# SCH_PicoCounter_v2.net
KiCad netlist of a schematic drawn in EasyEDA
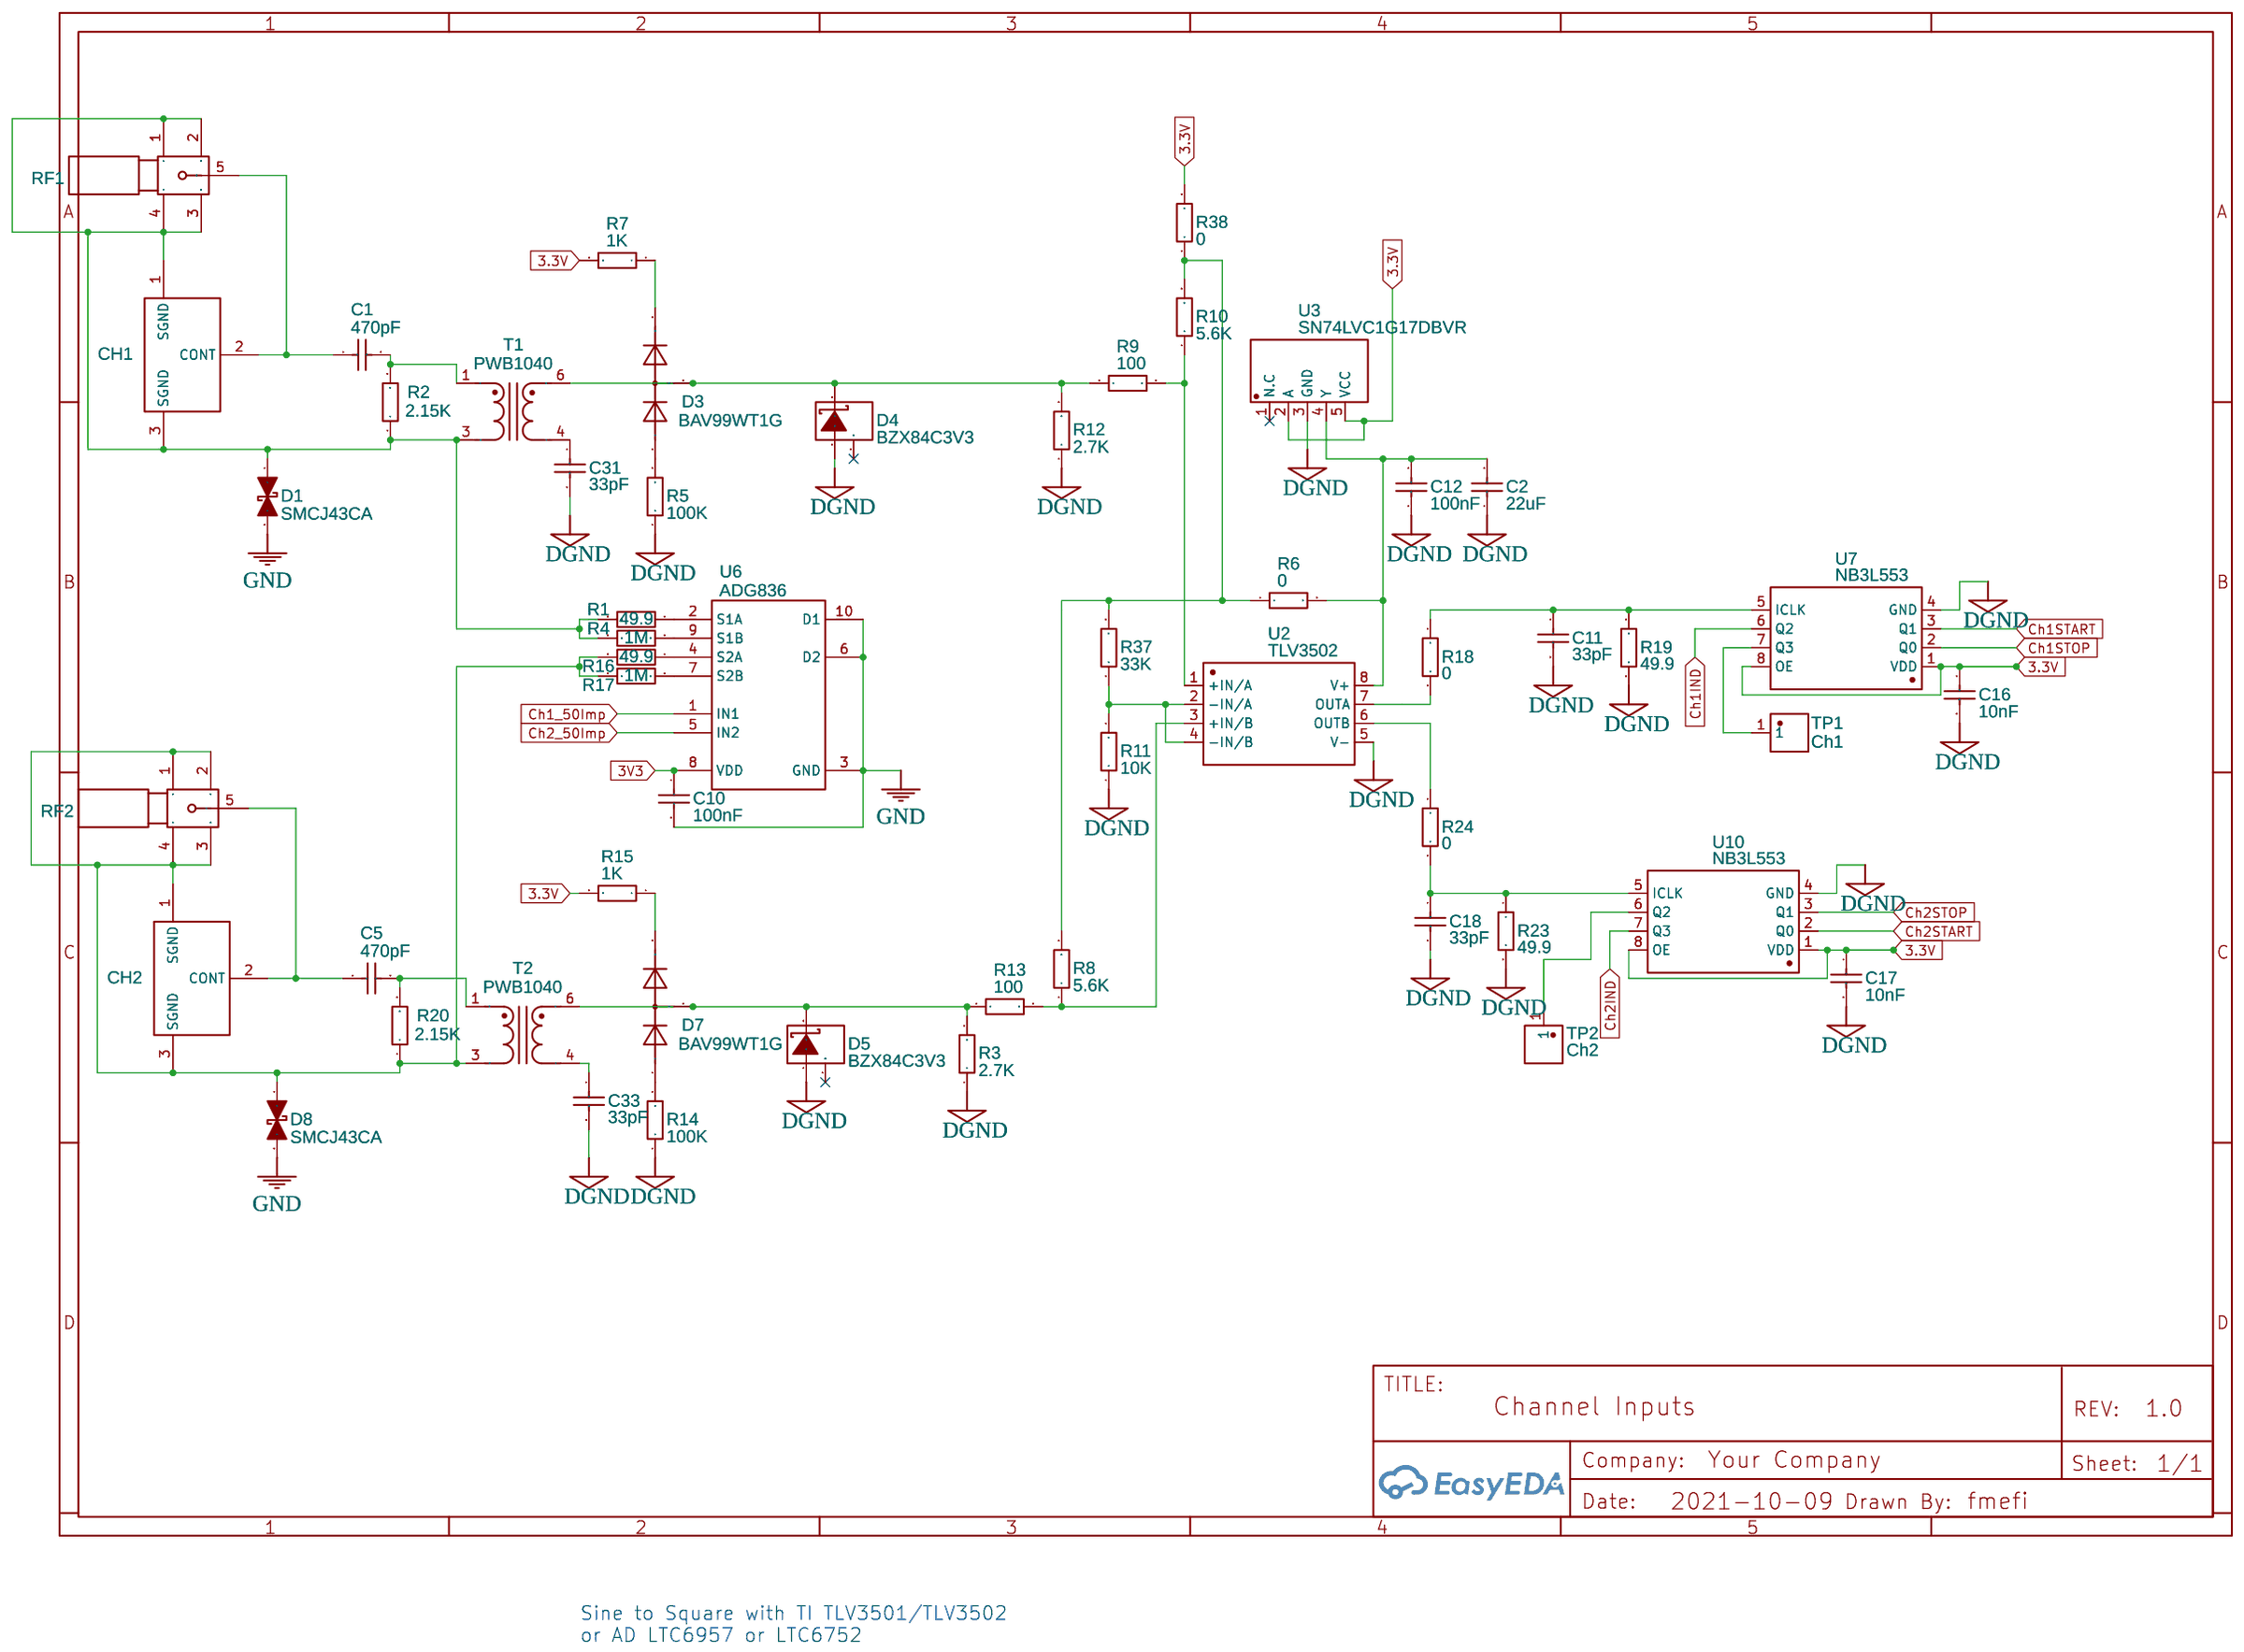
[diagram p0: Channel Inputs]
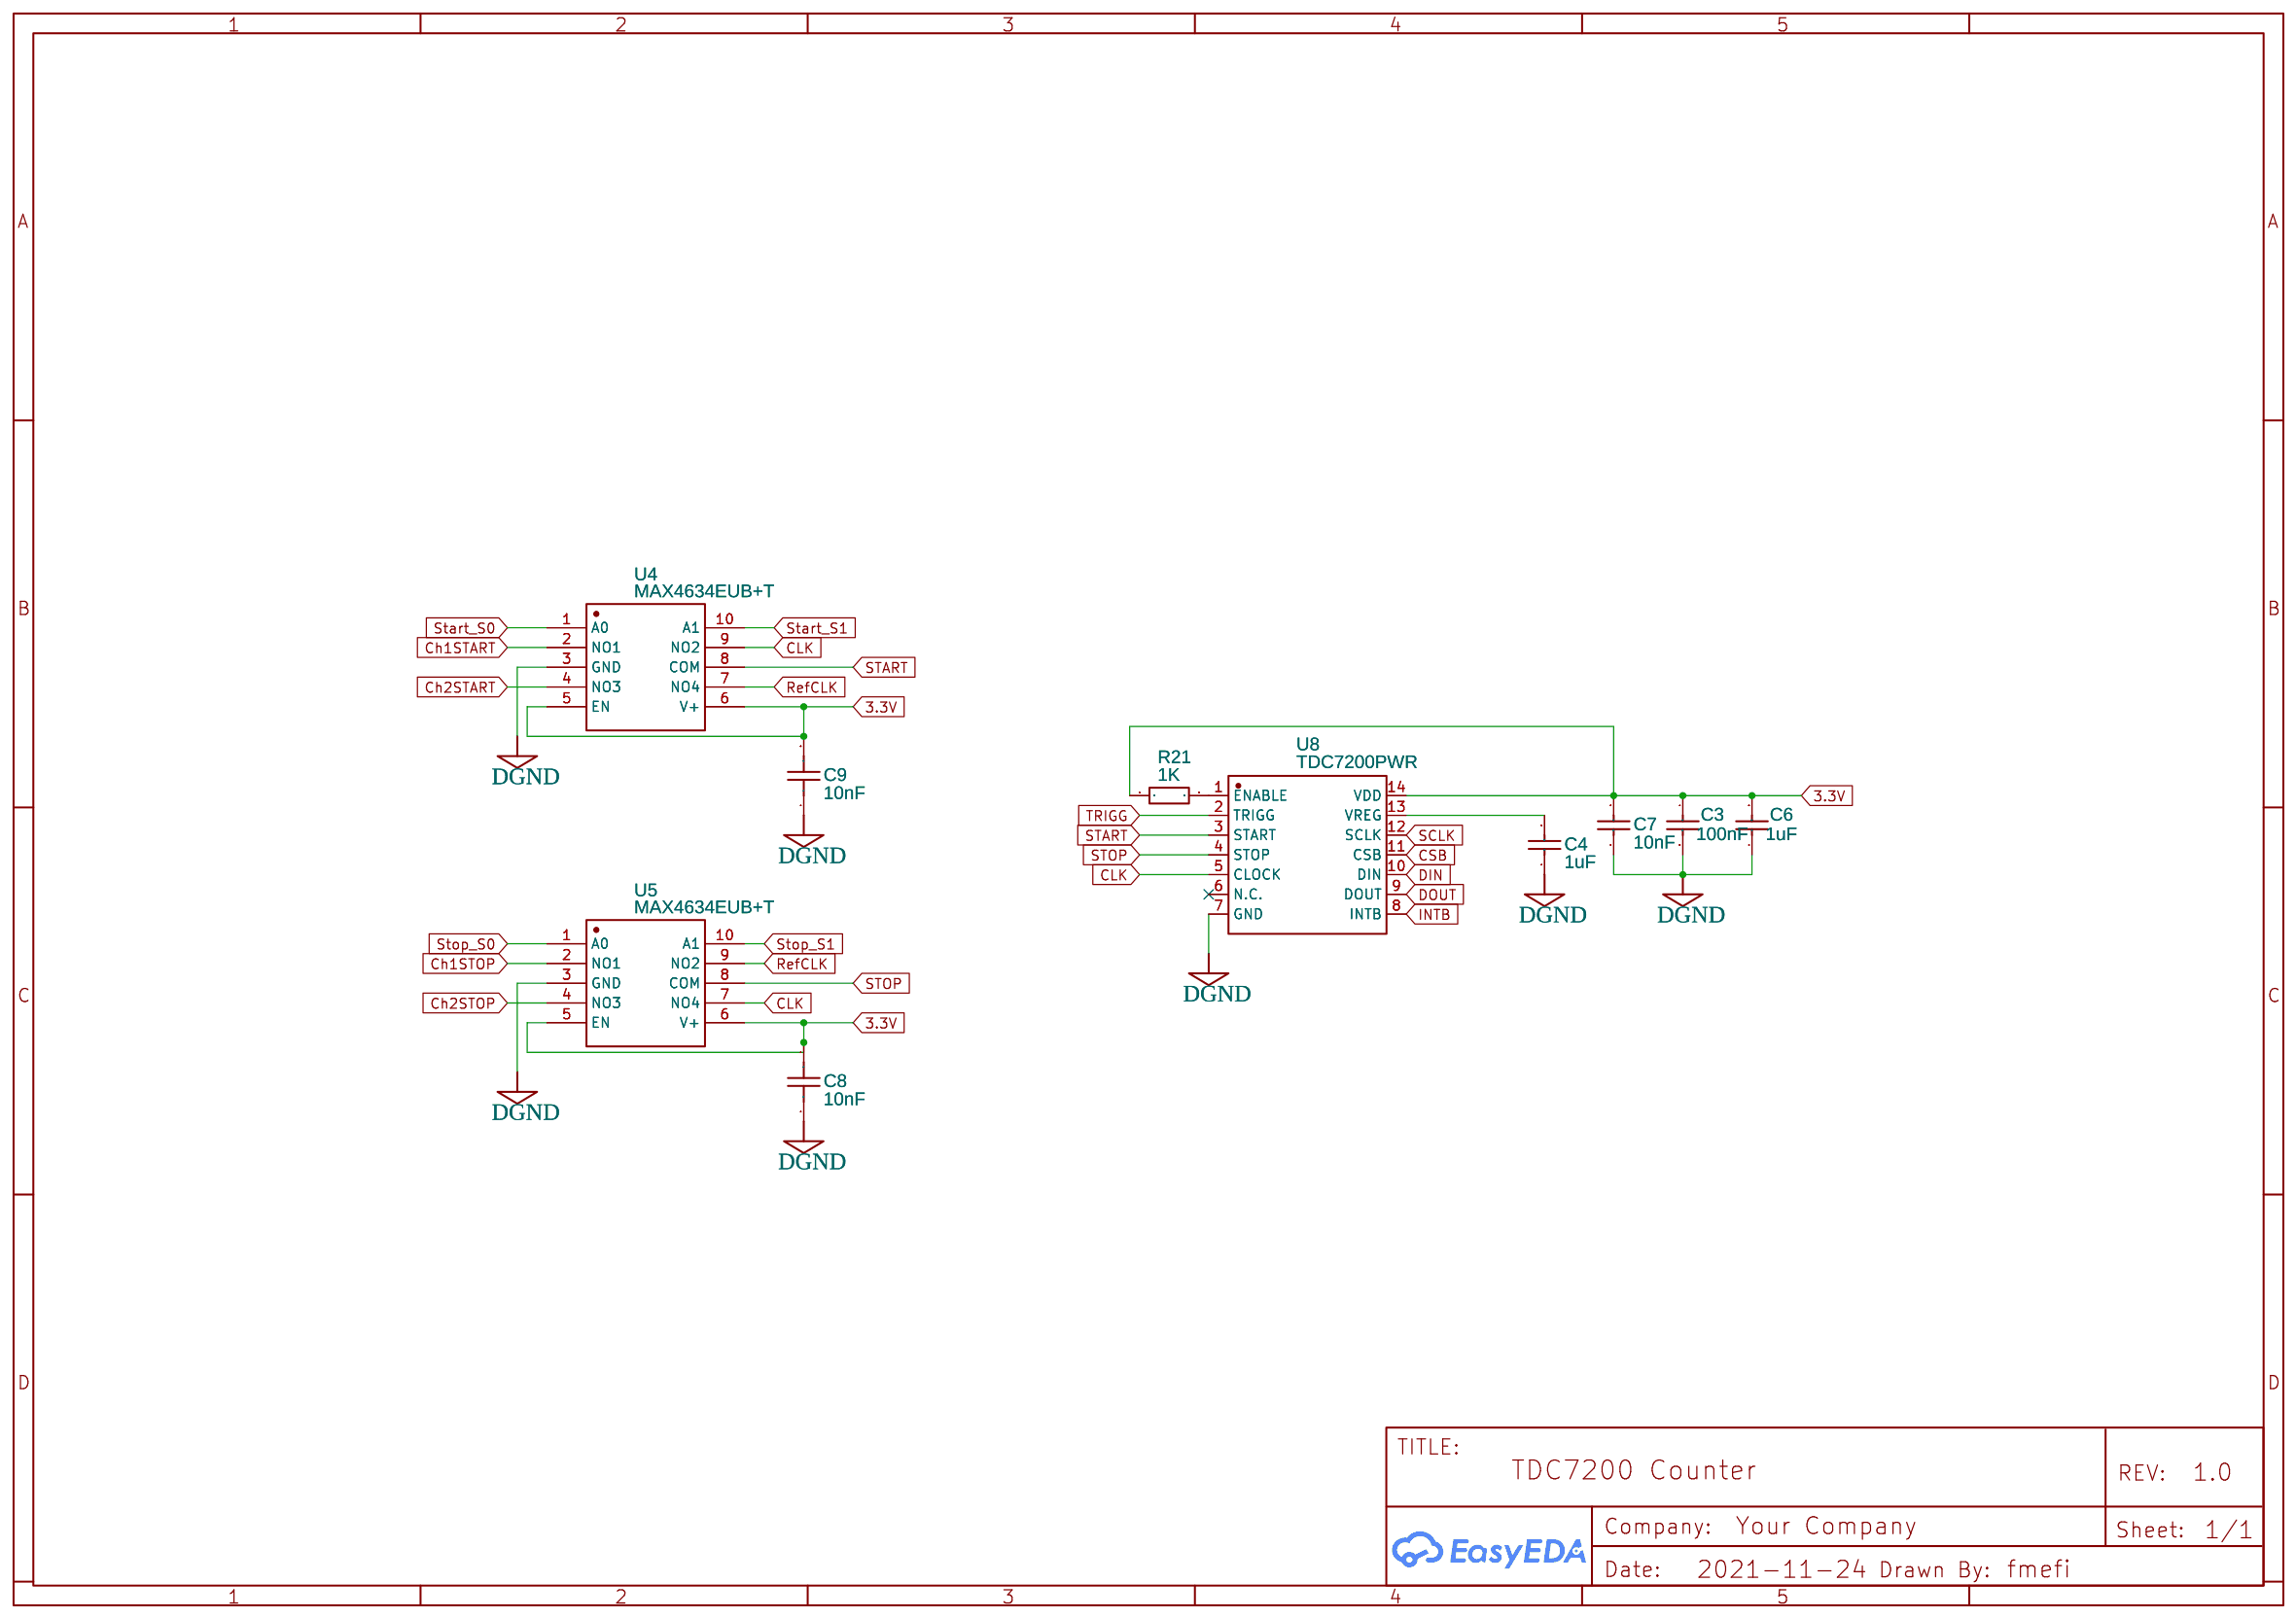
[diagram p1: TDC7200]
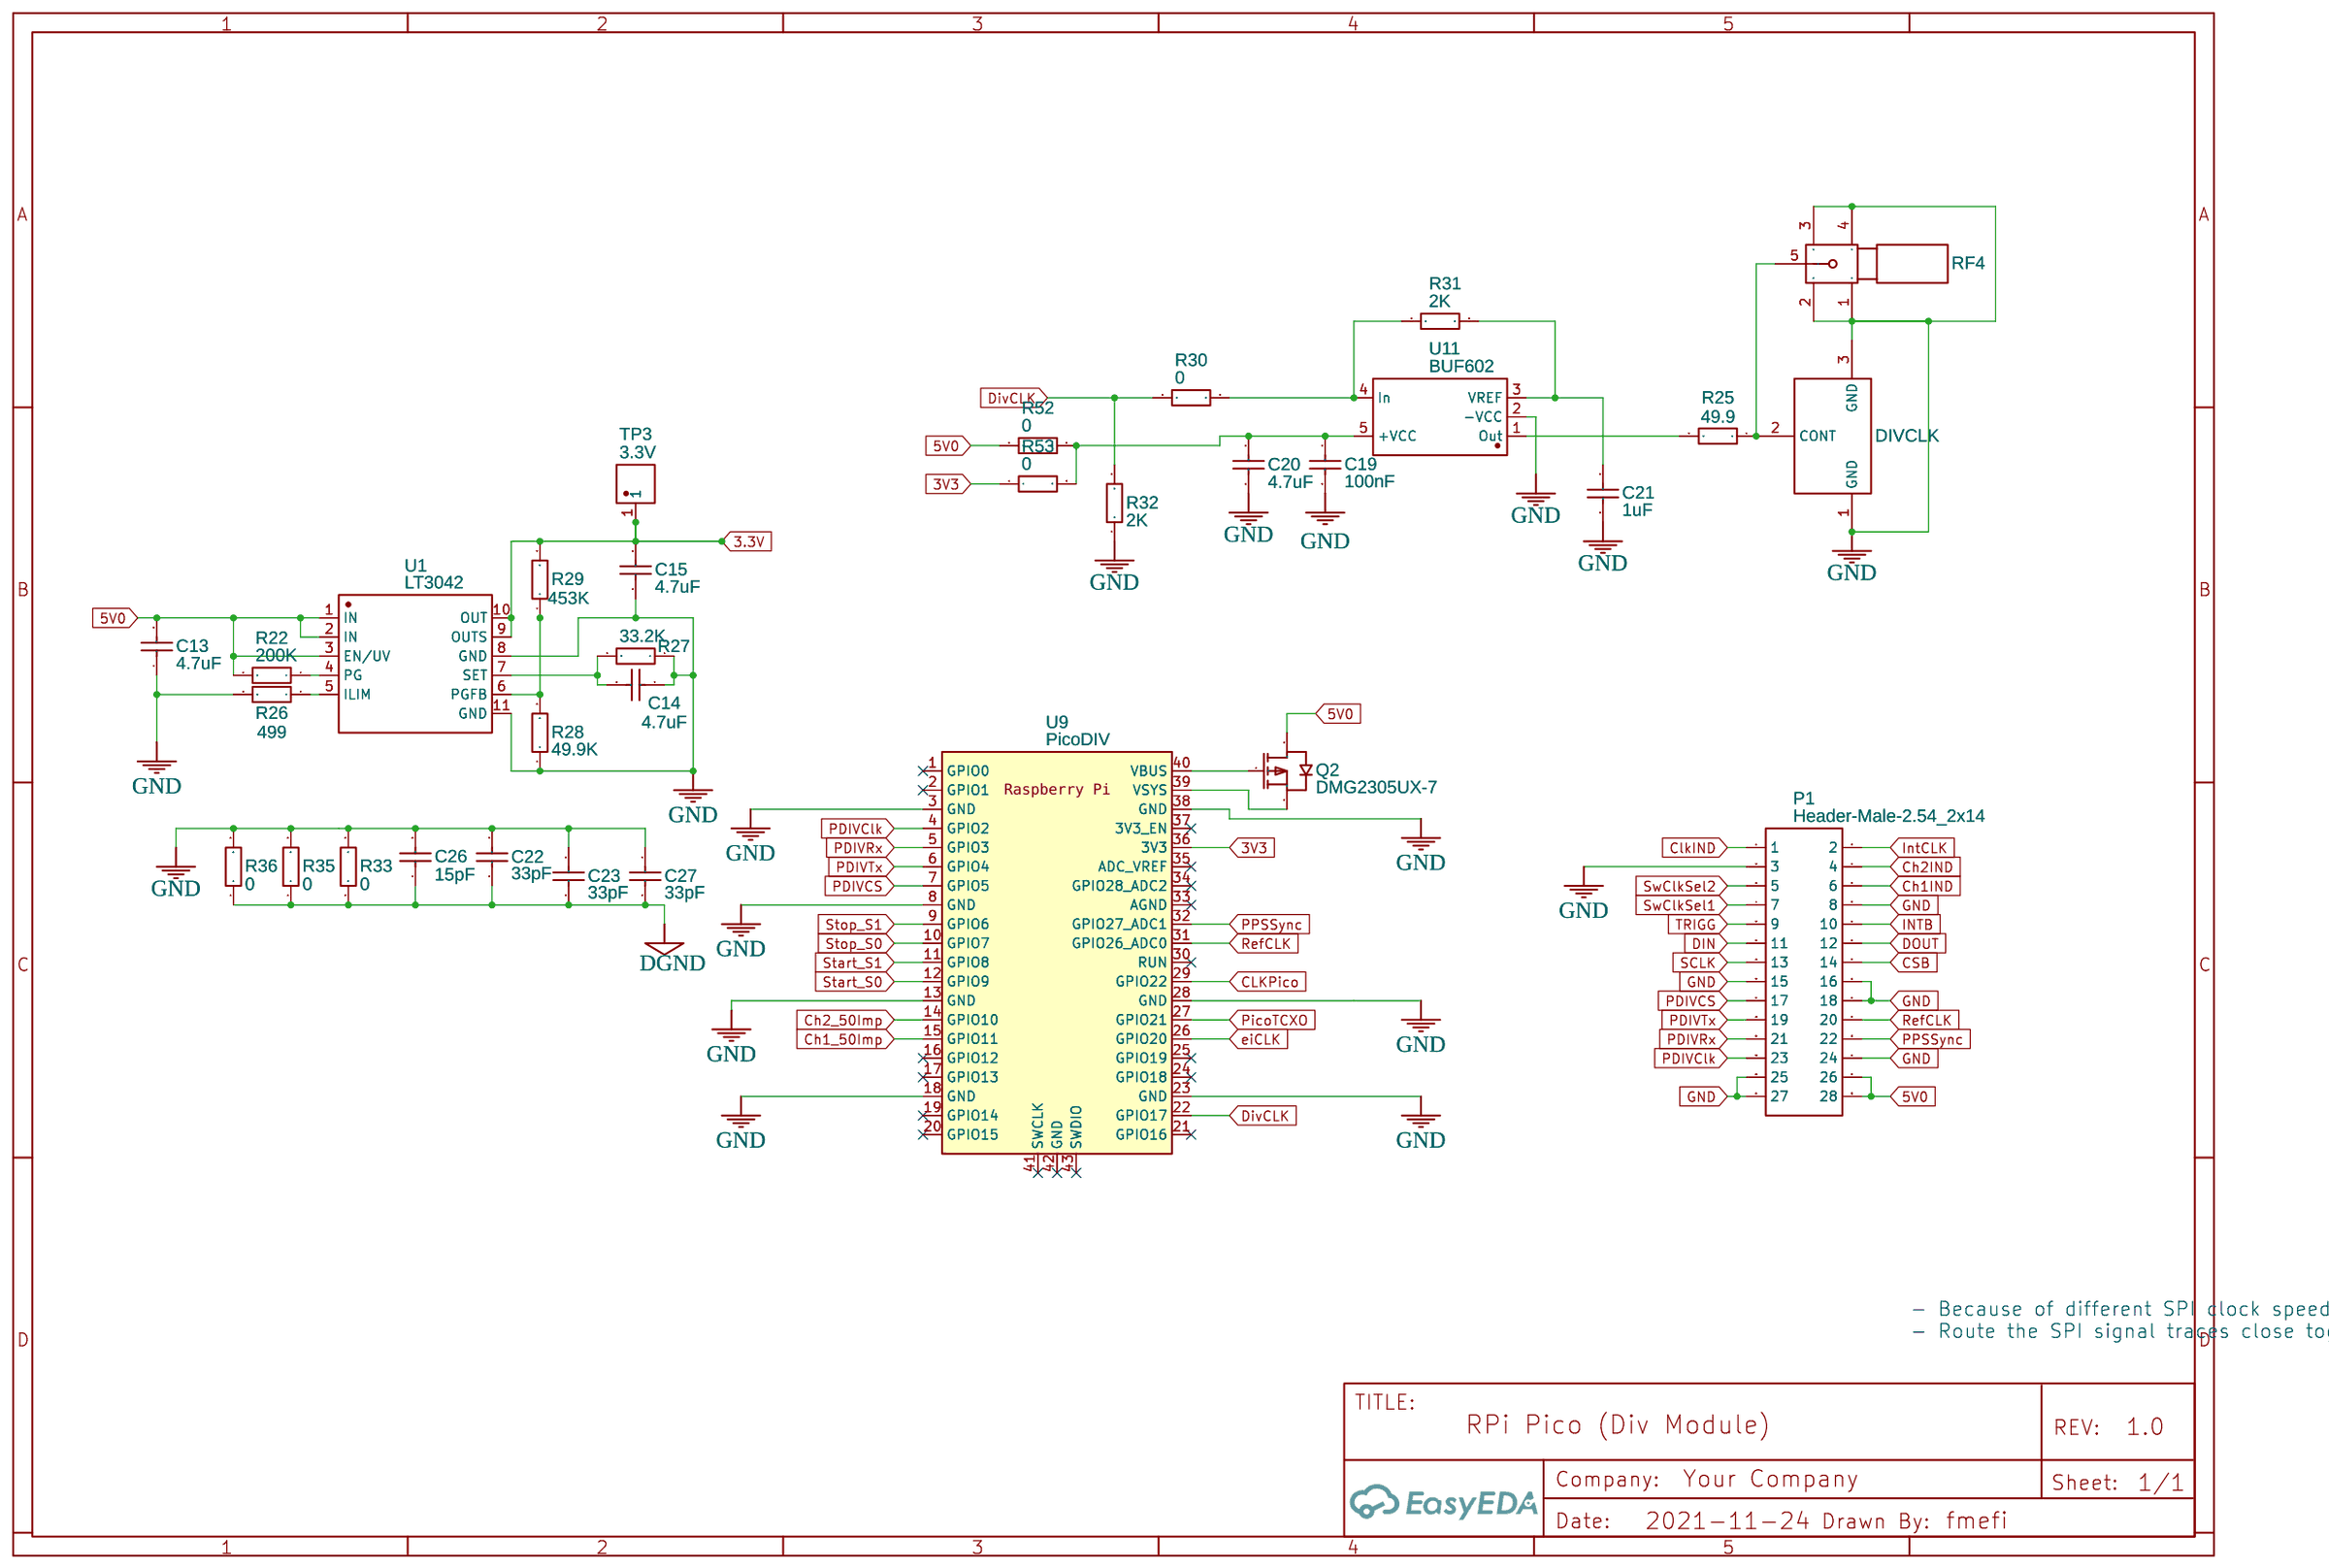
[diagram p2: RPi Pico]
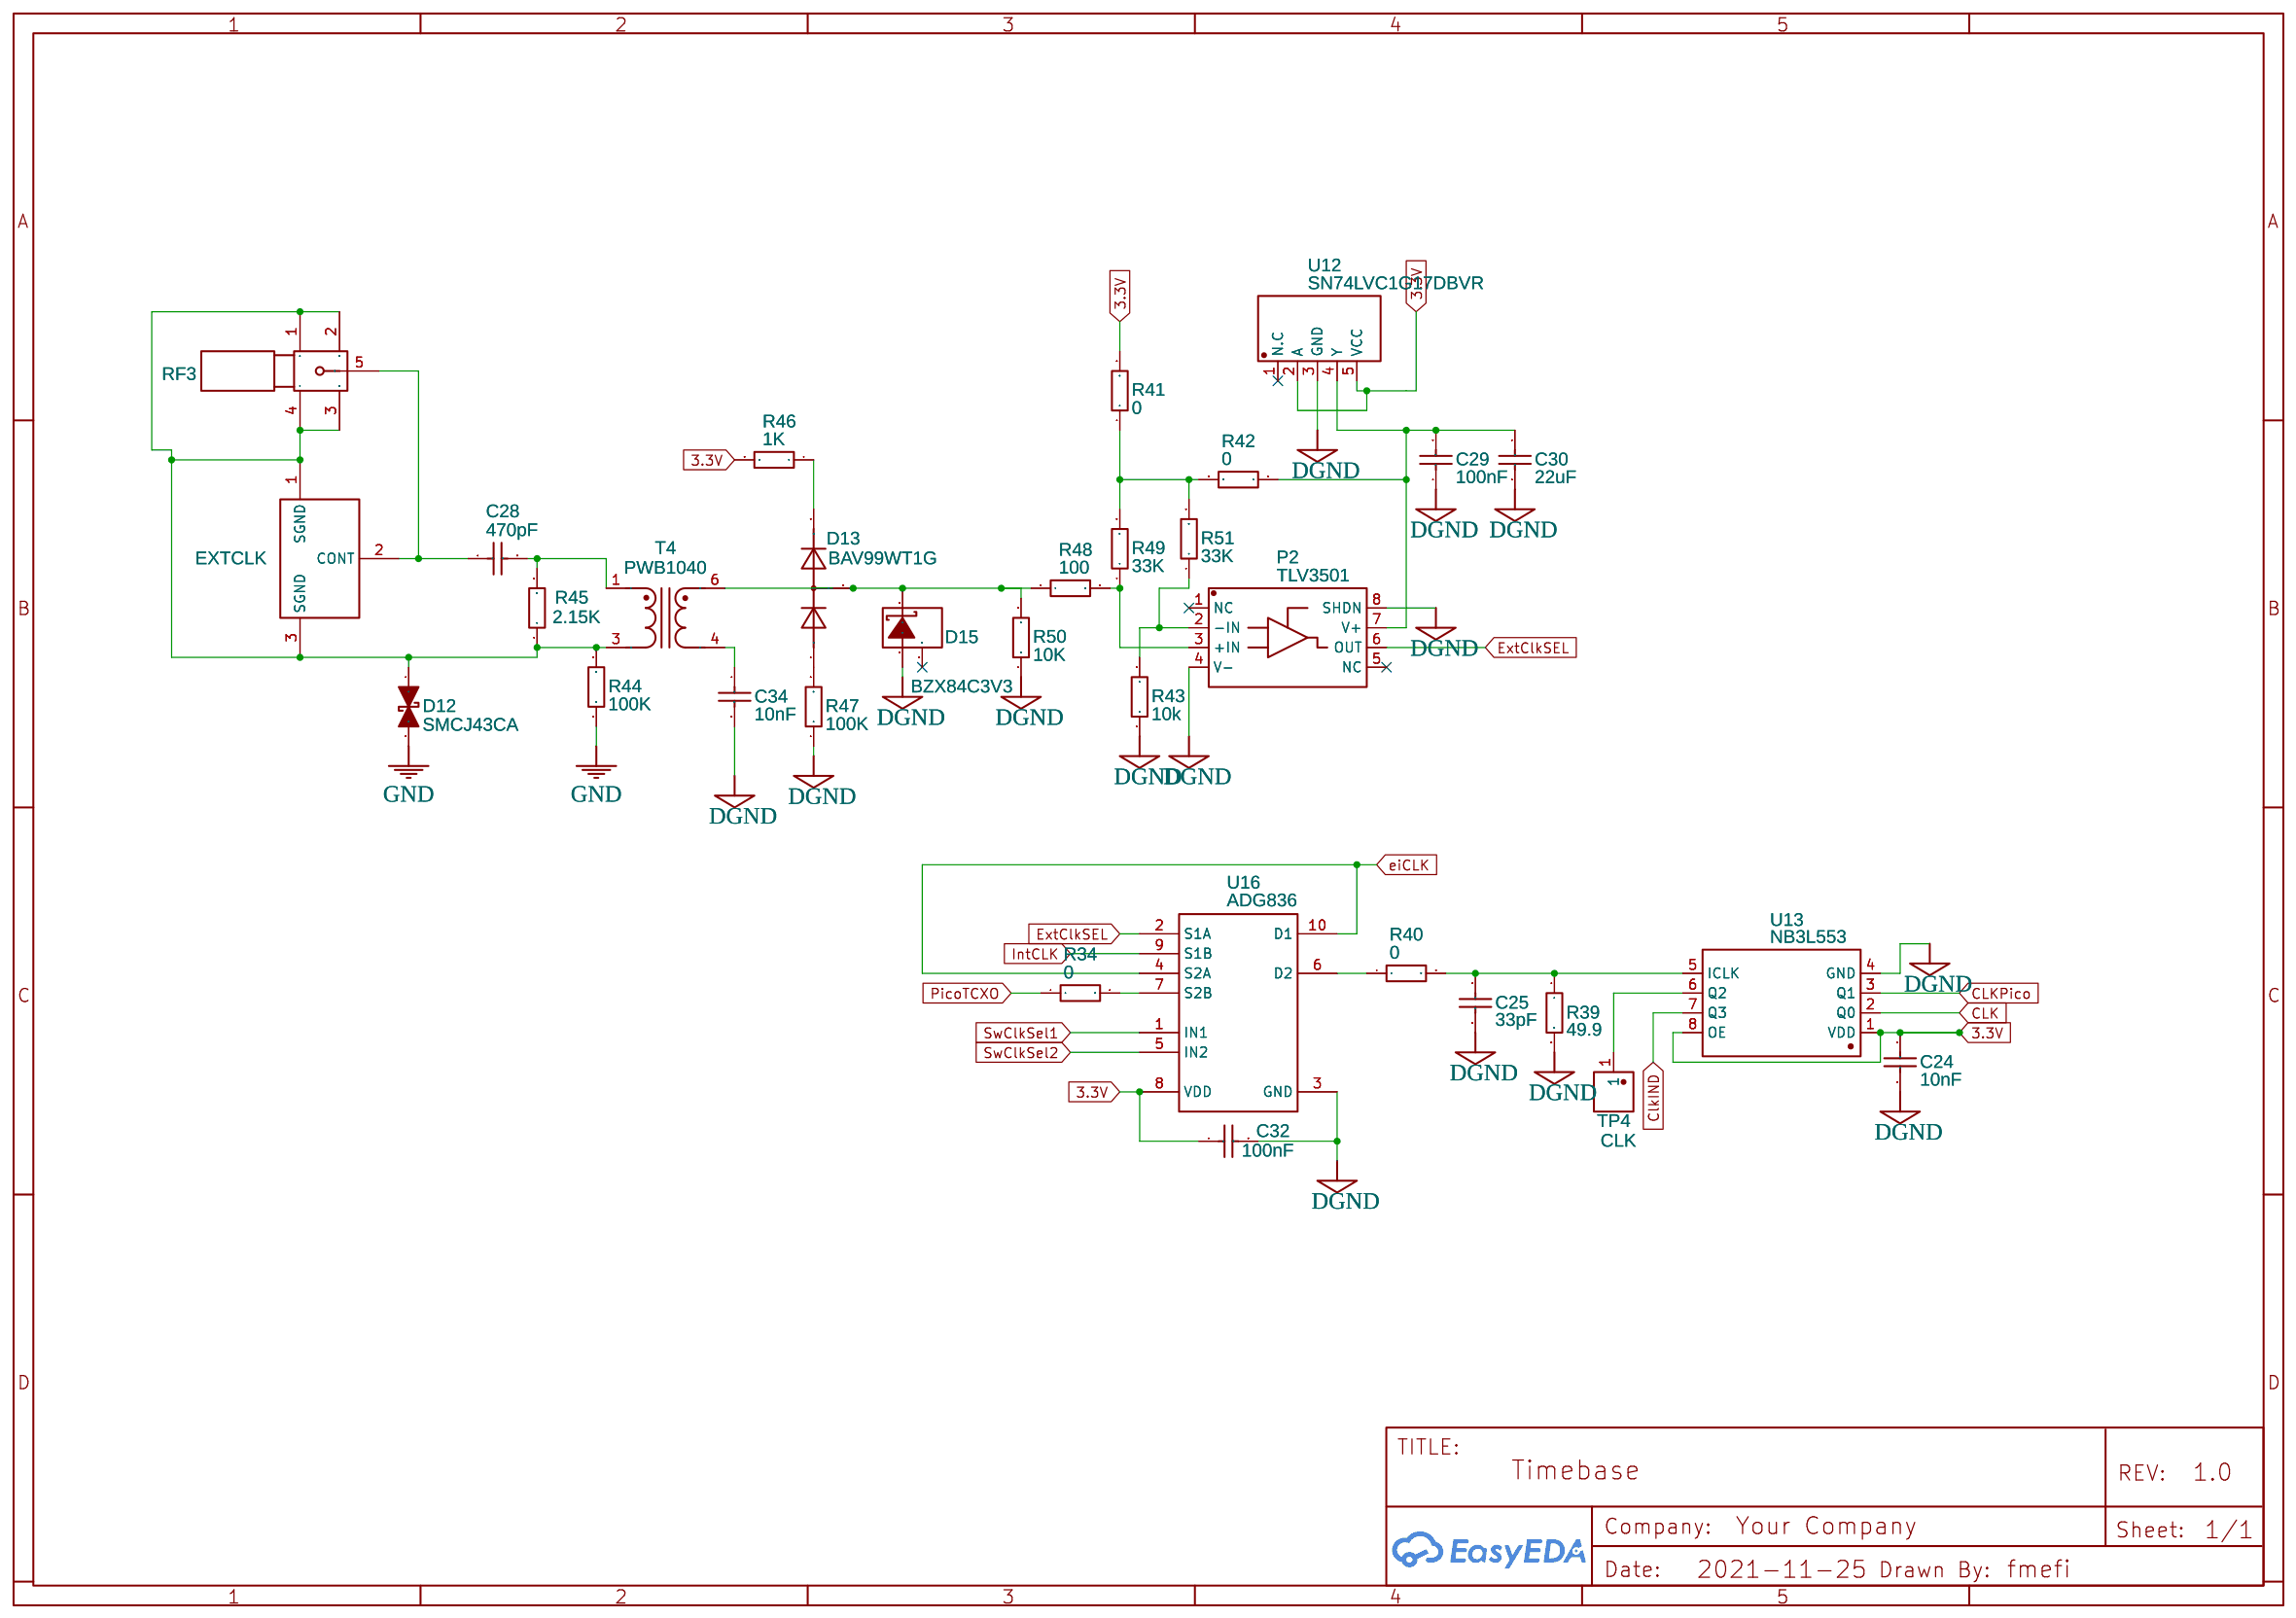
[diagram p3: Timebase]

(export (version "E")
  (design (tool "Eeschema 10.0.6"))
  (components
    (comp (ref "C1")
      (value "470pF")
      (fields
        (field (name "BOM_Manufacturer Part") "CL21C471JBANNNC")
        (field (name "BOM_Supplier Part") "C28256")
      )
      (libsource (lib "") (part "CL21C471JBANNNC"))
    )
    (comp (ref "C2")
      (value "22uF")
      (fields
        (field (name "BOM_Manufacturer Part") "CL21A226MPQNNNE")
        (field (name "BOM_Supplier Part") "C29277")
      )
      (libsource (lib "") (part "CL21A226MPQNNNE"))
    )
    (comp (ref "C5")
      (value "470pF")
      (fields
        (field (name "BOM_Manufacturer Part") "CL21C471JBANNNC")
        (field (name "BOM_Supplier Part") "C28256")
      )
      (libsource (lib "") (part "CL21C471JBANNNC"))
    )
    (comp (ref "C10")
      (value "100nF")
      (fields
        (field (name "BOM_Manufacturer Part") "CC0805KRX7R9BB104")
        (field (name "BOM_Supplier Part") "C49678")
      )
      (libsource (lib "") (part "CC0805KRX7R9BB104"))
    )
    (comp (ref "C11")
      (value "33pF")
      (fields
        (field (name "BOM_Manufacturer Part") "CL21C330JBANNNC")
        (field (name "BOM_Supplier Part") "C1814")
      )
      (libsource (lib "") (part "CL21C330JBANNNC"))
    )
    (comp (ref "C12")
      (value "100nF")
      (fields
        (field (name "BOM_Manufacturer Part") "CC0805KRX7R9BB104")
        (field (name "BOM_Supplier Part") "C49678")
      )
      (libsource (lib "") (part "CC0805KRX7R9BB104_1"))
    )
    (comp (ref "C16")
      (value "10nF")
      (fields
        (field (name "BOM_Manufacturer Part") "CL21B103KBANNNC")
        (field (name "BOM_Supplier Part") "C1710")
      )
      (libsource (lib "") (part "CL21B103KBANNNC"))
    )
    (comp (ref "C17")
      (value "10nF")
      (fields
        (field (name "BOM_Manufacturer Part") "CL21B103KBANNNC")
        (field (name "BOM_Supplier Part") "C1710")
      )
      (libsource (lib "") (part "CL21B103KBANNNC"))
    )
    (comp (ref "C18")
      (value "33pF")
      (fields
        (field (name "BOM_Manufacturer Part") "CL21C330JBANNNC")
        (field (name "BOM_Supplier Part") "C1814")
      )
      (libsource (lib "") (part "CL21C330JBANNNC"))
    )
    (comp (ref "C31")
      (value "33pF")
      (fields
        (field (name "BOM_Manufacturer Part") "CL21C330JBANNNC")
        (field (name "BOM_Supplier Part") "C1814")
      )
      (libsource (lib "") (part "CL21C330JBANNNC"))
    )
    (comp (ref "C33")
      (value "33pF")
      (fields
        (field (name "BOM_Manufacturer Part") "CL21C330JBANNNC")
        (field (name "BOM_Supplier Part") "C1814")
      )
      (libsource (lib "") (part "CL21C330JBANNNC"))
    )
    (comp (ref "CH1")
      (value "ChA")
      (fields
        (field (name "BOM_Manufacturer Part") "KH-IPEX-K501-29")
        (field (name "BOM_Supplier Part") "C411563")
      )
      (libsource (lib "") (part "KH-IPEX-K501-29"))
    )
    (comp (ref "CH2")
      (value "ChA")
      (fields
        (field (name "BOM_Manufacturer Part") "KH-IPEX-K501-29")
        (field (name "BOM_Supplier Part") "C411563")
      )
      (libsource (lib "") (part "KH-IPEX-K501-29"))
    )
    (comp (ref "D1")
      (value "SMCJ43CA")
      (fields (field (name "BOM_Supplier Part") "C310053"))
      (libsource (lib "") (part "SMCJ43CA"))
    )
    (comp (ref "D3")
      (value "BAV99WT1G")
      (fields (field (name "BOM_Supplier Part") "C82078"))
      (libsource (lib "") (part "BAV99WT1G"))
    )
    (comp (ref "D4")
      (value "BZX84C3V3")
      (fields
        (field (name "BOM_Manufacturer Part") "SZBZX84C3V3LT1G")
        (field (name "BOM_Supplier Part") "C231240")
      )
      (libsource (lib "") (part "SZBZX84C3V3LT1G"))
    )
    (comp (ref "D5")
      (value "BZX84C3V3")
      (fields
        (field (name "BOM_Manufacturer Part") "SZBZX84C3V3LT1G")
        (field (name "BOM_Supplier Part") "C231240")
      )
      (libsource (lib "") (part "SZBZX84C3V3LT1G"))
    )
    (comp (ref "D7")
      (value "BAV99WT1G")
      (fields (field (name "BOM_Supplier Part") "C82078"))
      (libsource (lib "") (part "BAV99WT1G"))
    )
    (comp (ref "D8")
      (value "SMCJ43CA")
      (fields (field (name "BOM_Supplier Part") "C310053"))
      (libsource (lib "") (part "SMCJ43CA"))
    )
    (comp (ref "R1")
      (value "49.9")
      (fields
        (field (name "BOM_Manufacturer Part") "0805W8F499JT5E")
        (field (name "BOM_Supplier Part") "C17720")
      )
      (libsource (lib "") (part "0805W8F499JT5E"))
    )
    (comp (ref "R2")
      (value "2.15K")
      (fields
        (field (name "BOM_Manufacturer Part") "0805W8F2151T5E")
        (field (name "BOM_Supplier Part") "C17516")
      )
      (libsource (lib "") (part "0805W8F2151T5E"))
    )
    (comp (ref "R3")
      (value "2.7K")
      (fields
        (field (name "BOM_Manufacturer Part") "0805W8F2701T5E")
        (field (name "BOM_Supplier Part") "C17530")
      )
      (libsource (lib "") (part "0805W8F1002T5E"))
    )
    (comp (ref "R4")
      (value "1M")
      (fields
        (field (name "BOM_Manufacturer Part") "0805W8F1004T5E")
        (field (name "BOM_Supplier Part") "C17514")
      )
      (libsource (lib "") (part "0805W8F1004T5E"))
    )
    (comp (ref "R5")
      (value "100K")
      (fields
        (field (name "BOM_Manufacturer Part") "0805W8F1003T5E")
        (field (name "BOM_Supplier Part") "C17407")
      )
      (libsource (lib "") (part "0805W8F1003T5E"))
    )
    (comp (ref "R6")
      (value "0")
      (fields
        (field (name "BOM_Manufacturer Part") "0805W8F0000T5E")
        (field (name "BOM_Supplier Part") "C17477")
      )
      (libsource (lib "") (part "0805W8F0000T5E_2"))
    )
    (comp (ref "R7")
      (value "1K")
      (fields
        (field (name "BOM_Manufacturer Part") "0805W8F1001T5E")
        (field (name "BOM_Supplier Part") "C17513")
      )
      (libsource (lib "") (part "0805W8F1001T5E"))
    )
    (comp (ref "R8")
      (value "5.6K")
      (fields
        (field (name "BOM_Manufacturer Part") "0805W8F5601T5E")
        (field (name "BOM_Supplier Part") "C4382")
      )
      (libsource (lib "") (part "0805W8F1003T5E"))
    )
    (comp (ref "R9")
      (value "100")
      (fields
        (field (name "BOM_Manufacturer Part") "0805W8F1000T5E")
        (field (name "BOM_Supplier Part") "C17408")
      )
      (libsource (lib "") (part "0805W8F1000T5E"))
    )
    (comp (ref "R10")
      (value "5.6K")
      (fields
        (field (name "BOM_Manufacturer Part") "0805W8F5601T5E")
        (field (name "BOM_Supplier Part") "C4382")
      )
      (libsource (lib "") (part "0805W8F1003T5E"))
    )
    (comp (ref "R11")
      (value "10K")
      (fields
        (field (name "BOM_Manufacturer Part") "0805W8F1002T5E")
        (field (name "BOM_Supplier Part") "C17414")
      )
      (libsource (lib "") (part "0805W8F1000T5E_1"))
    )
    (comp (ref "R12")
      (value "2.7K")
      (fields
        (field (name "BOM_Manufacturer Part") "0805W8F2701T5E")
        (field (name "BOM_Supplier Part") "C17530")
      )
      (libsource (lib "") (part "0805W8F1002T5E"))
    )
    (comp (ref "R13")
      (value "100")
      (fields
        (field (name "BOM_Manufacturer Part") "0805W8F1000T5E")
        (field (name "BOM_Supplier Part") "C17408")
      )
      (libsource (lib "") (part "0805W8F1000T5E"))
    )
    (comp (ref "R14")
      (value "100K")
      (fields
        (field (name "BOM_Manufacturer Part") "0805W8F1003T5E")
        (field (name "BOM_Supplier Part") "C17407")
      )
      (libsource (lib "") (part "0805W8F1003T5E"))
    )
    (comp (ref "R15")
      (value "1K")
      (fields
        (field (name "BOM_Manufacturer Part") "0805W8F1001T5E")
        (field (name "BOM_Supplier Part") "C17513")
      )
      (libsource (lib "") (part "0805W8F1001T5E"))
    )
    (comp (ref "R16")
      (value "49.9")
      (fields
        (field (name "BOM_Manufacturer Part") "0805W8F499JT5E")
        (field (name "BOM_Supplier Part") "C17720")
      )
      (libsource (lib "") (part "0805W8F499JT5E"))
    )
    (comp (ref "R17")
      (value "1M")
      (fields
        (field (name "BOM_Manufacturer Part") "0805W8F1004T5E")
        (field (name "BOM_Supplier Part") "C17514")
      )
      (libsource (lib "") (part "0805W8F1004T5E"))
    )
    (comp (ref "R18")
      (value "0")
      (fields
        (field (name "BOM_Manufacturer Part") "0805W8F0000T5E")
        (field (name "BOM_Supplier Part") "C17477")
      )
      (libsource (lib "") (part "0805W8F0000T5E_1"))
    )
    (comp (ref "R19")
      (value "49.9")
      (fields
        (field (name "BOM_Manufacturer Part") "0805W8F499JT5E")
        (field (name "BOM_Supplier Part") "C17720")
      )
      (libsource (lib "") (part "0805W8F499JT5E_1"))
    )
    (comp (ref "R20")
      (value "2.15K")
      (fields
        (field (name "BOM_Manufacturer Part") "0805W8F2151T5E")
        (field (name "BOM_Supplier Part") "C17516")
      )
      (libsource (lib "") (part "0805W8F2151T5E"))
    )
    (comp (ref "R23")
      (value "49.9")
      (fields
        (field (name "BOM_Manufacturer Part") "0805W8F499JT5E")
        (field (name "BOM_Supplier Part") "C17720")
      )
      (libsource (lib "") (part "0805W8F499JT5E_1"))
    )
    (comp (ref "R24")
      (value "0")
      (fields
        (field (name "BOM_Manufacturer Part") "0805W8F0000T5E")
        (field (name "BOM_Supplier Part") "C17477")
      )
      (libsource (lib "") (part "0805W8F0000T5E_1"))
    )
    (comp (ref "R37")
      (value "33K")
      (fields
        (field (name "BOM_Manufacturer Part") "0805W8F3302T5E")
        (field (name "BOM_Supplier Part") "C17633")
      )
      (libsource (lib "") (part "0805W8F1003T5E"))
    )
    (comp (ref "R38")
      (value "0")
      (fields
        (field (name "BOM_Manufacturer Part") "0805W8F0000T5E")
        (field (name "BOM_Supplier Part") "C17477")
      )
      (libsource (lib "") (part "0805W8F0000T5E"))
    )
    (comp (ref "RF1")
      (value "KH-SMA-KE8-G")
      (fields (field (name "BOM_Supplier Part") "C530661"))
      (libsource (lib "") (part "KH-SMA-KE8-G"))
    )
    (comp (ref "RF2")
      (value "KH-SMA-KE8-G")
      (fields (field (name "BOM_Supplier Part") "C530661"))
      (libsource (lib "") (part "KH-SMA-KE8-G"))
    )
    (comp (ref "T1")
      (value "PWB1040")
      (fields
        (field (name "BOM_Manufacturer Part") "PE-68386NLT")
        (field (name "BOM_Supplier Part") "C581397")
      )
      (libsource (lib "") (part "PWB1040 COILCRAFT"))
    )
    (comp (ref "T2")
      (value "PWB1040")
      (fields
        (field (name "BOM_Manufacturer Part") "PE-68386NLT")
        (field (name "BOM_Supplier Part") "C581397")
      )
      (libsource (lib "") (part "PWB1040 COILCRAFT"))
    )
    (comp (ref "TP1")
      (value "Ch1")
      (fields (field (name "BOM_Manufacturer Part") "RCUCTE") (field (name "BOM_Supplier Part") "C159867"))
      (libsource (lib "") (part "RCUCTE_1"))
    )
    (comp (ref "TP2")
      (value "Ch2")
      (fields (field (name "BOM_Manufacturer Part") "RCUCTE") (field (name "BOM_Supplier Part") "C159867"))
      (libsource (lib "") (part "RCUCTE"))
    )
    (comp (ref "U2")
      (value "TLV3502")
      (fields
        (field (name "BOM_Manufacturer Part") "TLV3502AIDR")
        (field (name "BOM_Supplier Part") "C131165")
      )
      (libsource (lib "") (part "TLV3502AIDR"))
    )
    (comp (ref "U3")
      (value "SN74LVC1G17DBVR")
      (fields (field (name "BOM_Supplier Part") "C7836"))
      (libsource (lib "") (part "SN74LVC1G17DBVR"))
    )
    (comp (ref "U6")
      (value "ADG836")
      (fields
        (field (name "BOM_Manufacturer Part") "ADG836YRMZ")
        (field (name "BOM_Supplier Part") "C208153")
      )
      (libsource (lib "") (part "ADG836YRMZ"))
    )
    (comp (ref "U7")
      (value "NB3L553")
      (fields
        (field (name "BOM_Manufacturer Part") "NB3L553DR2G")
        (field (name "BOM_Supplier Part") "C145512")
      )
      (libsource (lib "") (part "NB3L553DR2G"))
    )
    (comp (ref "U10")
      (value "NB3L553")
      (fields
        (field (name "BOM_Manufacturer Part") "NB3L553DR2G")
        (field (name "BOM_Supplier Part") "C145512")
      )
      (libsource (lib "") (part "NB3L553DR2G"))
    )
    (comp (ref "C3")
      (value "100nF")
      (fields
        (field (name "BOM_Manufacturer Part") "CC0805KRX7R9BB104")
        (field (name "BOM_Supplier Part") "C49678")
      )
      (libsource (lib "") (part "CC0805KRX7R9BB104"))
    )
    (comp (ref "C4")
      (value "1uF")
      (fields
        (field (name "BOM_Manufacturer Part") "CL21B105KBFNNNE")
        (field (name "BOM_Supplier Part") "C28323")
      )
      (libsource (lib "") (part "CL21B105KBFNNNE"))
    )
    (comp (ref "C6")
      (value "1uF")
      (fields
        (field (name "BOM_Manufacturer Part") "CL21B105KBFNNNE")
        (field (name "BOM_Supplier Part") "C28323")
      )
      (libsource (lib "") (part "CL21B105KBFNNNE"))
    )
    (comp (ref "C7")
      (value "10nF")
      (fields
        (field (name "BOM_Manufacturer Part") "CL21B103KBANNNC")
        (field (name "BOM_Supplier Part") "C1710")
      )
      (libsource (lib "") (part "CL21B103KBANNNC"))
    )
    (comp (ref "C8")
      (value "10nF")
      (fields
        (field (name "BOM_Manufacturer Part") "CC0805KRX7R9BB103")
        (field (name "BOM_Supplier Part") "C83170")
      )
      (libsource (lib "") (part "CC0805KRX7R9BB103"))
    )
    (comp (ref "C9")
      (value "10nF")
      (fields
        (field (name "BOM_Manufacturer Part") "CC0805KRX7R9BB103")
        (field (name "BOM_Supplier Part") "C83170")
      )
      (libsource (lib "") (part "CC0805KRX7R9BB103"))
    )
    (comp (ref "R21")
      (value "1K")
      (fields
        (field (name "BOM_Manufacturer Part") "0805W8F1001T5E")
        (field (name "BOM_Supplier Part") "C17513")
      )
      (libsource (lib "") (part "0805W8F1001T5E"))
    )
    (comp (ref "U4")
      (value "MAX4634EUB+T")
      (fields (field (name "BOM_Supplier Part") "C118342"))
      (libsource (lib "") (part "MAX4634EUB+T"))
    )
    (comp (ref "U5")
      (value "MAX4634EUB+T")
      (fields (field (name "BOM_Supplier Part") "C118342"))
      (libsource (lib "") (part "MAX4634EUB+T"))
    )
    (comp (ref "U8")
      (value "TDC7200PWR")
      (fields (field (name "BOM_Supplier Part") "C2653139"))
      (libsource (lib "") (part "TDC7200PWR"))
    )
    (comp (ref "C13")
      (value "4.7uF")
      (fields
        (field (name "BOM_Manufacturer Part") "CL21A475KAQNNNE")
        (field (name "BOM_Supplier Part") "C1779")
      )
      (libsource (lib "") (part "CL21A475KAQNNNE_2"))
    )
    (comp (ref "C14")
      (value "4.7uF")
      (fields
        (field (name "BOM_Manufacturer Part") "CL21A475KAQNNNE")
        (field (name "BOM_Supplier Part") "C1779")
      )
      (libsource (lib "") (part "CL21A475KAQNNNE_1"))
    )
    (comp (ref "C15")
      (value "4.7uF")
      (fields
        (field (name "BOM_Manufacturer Part") "CL21A475KAQNNNE")
        (field (name "BOM_Supplier Part") "C1779")
      )
      (libsource (lib "") (part "CL21A475KAQNNNE_2"))
    )
    (comp (ref "C19")
      (value "100nF")
      (fields
        (field (name "BOM_Manufacturer Part") "CC0805KRX7R9BB104")
        (field (name "BOM_Supplier Part") "C49678")
      )
      (libsource (lib "") (part "CC0805KRX7R9BB104"))
    )
    (comp (ref "C20")
      (value "4.7uF")
      (fields
        (field (name "BOM_Manufacturer Part") "CL21A475KAQNNNE")
        (field (name "BOM_Supplier Part") "C1779")
      )
      (libsource (lib "") (part "CL21A475KAQNNNE"))
    )
    (comp (ref "C21")
      (value "1uF")
      (fields
        (field (name "BOM_Manufacturer Part") "CL21B105KBFNNNE")
        (field (name "BOM_Supplier Part") "C28323")
      )
      (libsource (lib "") (part "CL21B105KBFNNNE"))
    )
    (comp (ref "C22")
      (value "33pF")
      (fields
        (field (name "BOM_Manufacturer Part") "CL21C330JBANNNC")
        (field (name "BOM_Supplier Part") "C1814")
      )
      (libsource (lib "") (part "CL21C330JBANNNC"))
    )
    (comp (ref "C23")
      (value "33pF")
      (fields
        (field (name "BOM_Manufacturer Part") "CL21C330JBANNNC")
        (field (name "BOM_Supplier Part") "C1814")
      )
      (libsource (lib "") (part "CL21C330JBANNNC"))
    )
    (comp (ref "C26")
      (value "15pF")
      (fields
        (field (name "BOM_Manufacturer Part") "CL21C150JBANNNC")
        (field (name "BOM_Supplier Part") "C1794")
      )
      (libsource (lib "") (part "CL21C150JBANNNC"))
    )
    (comp (ref "C27")
      (value "33pF")
      (fields
        (field (name "BOM_Manufacturer Part") "CL21C330JBANNNC")
        (field (name "BOM_Supplier Part") "C1814")
      )
      (libsource (lib "") (part "CL21C330JBANNNC"))
    )
    (comp (ref "DIVCLK")
      (value "DIVCLK")
      (fields
        (field (name "BOM_Manufacturer Part") "KH-IPEX-K501-29")
        (field (name "BOM_Supplier Part") "C411563")
      )
      (libsource (lib "") (part "KH-IPEX-K501-29"))
    )
    (comp (ref "P1")
      (value "Header-Male-2.54_2x14")
      (fields
        (field (name "BOM_Manufacturer Part") "210R-2*14PCurved needle Gold-plated black")
        (field (name "BOM_Supplier Part") "C124368")
      )
      (libsource (lib "") (part "Header-Male-2.54_2x14"))
    )
    (comp (ref "Q2")
      (value "DMG2305UX-7")
      (fields (field (name "BOM_Supplier Part") "C150470"))
      (libsource (lib "") (part "DMG2305UX-7"))
    )
    (comp (ref "R22")
      (value "200K")
      (fields
        (field (name "BOM_Manufacturer Part") "0805W8F2003T5E")
        (field (name "BOM_Supplier Part") "C17539")
      )
      (libsource (lib "") (part "0805W8F2003T5E"))
    )
    (comp (ref "R25")
      (value "49.9")
      (fields
        (field (name "BOM_Manufacturer Part") "0805W8F499JT5E")
        (field (name "BOM_Supplier Part") "C17720")
      )
      (libsource (lib "") (part "0805W8F499JT5E"))
    )
    (comp (ref "R26")
      (value "499")
      (fields
        (field (name "BOM_Manufacturer Part") "0805W8F4990T5E")
        (field (name "BOM_Supplier Part") "C17722")
      )
      (libsource (lib "") (part "0805W8F4990T5E"))
    )
    (comp (ref "R27")
      (value "33.2K")
      (fields
        (field (name "BOM_Manufacturer Part") "0805W8F3322T5E")
        (field (name "BOM_Supplier Part") "C37252")
      )
      (libsource (lib "") (part "0805W8F3322T5E"))
    )
    (comp (ref "R28")
      (value "49.9K")
      (fields
        (field (name "BOM_Manufacturer Part") "0805W8F4992T5E")
        (field (name "BOM_Supplier Part") "C17719")
      )
      (libsource (lib "") (part "0805W8F4992T5E"))
    )
    (comp (ref "R29")
      (value "453K")
      (fields
        (field (name "BOM_Manufacturer Part") "0805W8F4533T5E")
        (field (name "BOM_Supplier Part") "C17702")
      )
      (libsource (lib "") (part "0805W8F4533T5E"))
    )
    (comp (ref "R30")
      (value "0")
      (fields
        (field (name "BOM_Manufacturer Part") "0805W8F0000T5E")
        (field (name "BOM_Supplier Part") "C17477")
      )
      (libsource (lib "") (part "0805W8F0000T5E_1"))
    )
    (comp (ref "R31")
      (value "2K")
      (fields
        (field (name "BOM_Manufacturer Part") "0805W8F2001T5E")
        (field (name "BOM_Supplier Part") "C17604")
      )
      (libsource (lib "") (part "0805W8F2001T5E_1"))
    )
    (comp (ref "R32")
      (value "2K")
      (fields
        (field (name "BOM_Manufacturer Part") "0805W8F2001T5E")
        (field (name "BOM_Supplier Part") "C17604")
      )
      (libsource (lib "") (part "0805W8F2001T5E"))
    )
    (comp (ref "R33")
      (value "0")
      (fields
        (field (name "BOM_Manufacturer Part") "0805W8F0000T5E")
        (field (name "BOM_Supplier Part") "C17477")
      )
      (libsource (lib "") (part "0805W8F0000T5E"))
    )
    (comp (ref "R35")
      (value "0")
      (fields
        (field (name "BOM_Manufacturer Part") "0805W8F0000T5E")
        (field (name "BOM_Supplier Part") "C17477")
      )
      (libsource (lib "") (part "0805W8F0000T5E"))
    )
    (comp (ref "R36")
      (value "0")
      (fields
        (field (name "BOM_Manufacturer Part") "0805W8F0000T5E")
        (field (name "BOM_Supplier Part") "C17477")
      )
      (libsource (lib "") (part "0805W8F0000T5E"))
    )
    (comp (ref "R52")
      (value "0")
      (fields
        (field (name "BOM_Manufacturer Part") "0805W8F0000T5E")
        (field (name "BOM_Supplier Part") "C17477")
      )
      (libsource (lib "") (part "0805W8F0000T5E_1"))
    )
    (comp (ref "R53")
      (value "0")
      (fields
        (field (name "BOM_Manufacturer Part") "0805W8F0000T5E")
        (field (name "BOM_Supplier Part") "C17477")
      )
      (libsource (lib "") (part "0805W8F0000T5E_1"))
    )
    (comp (ref "RF4")
      (value "KH-SMA-KE8-G")
      (fields (field (name "BOM_Supplier Part") "C530661"))
      (libsource (lib "") (part "KH-SMA-KE8-G"))
    )
    (comp (ref "TP3")
      (value "3.3V")
      (fields (field (name "BOM_Manufacturer Part") "RCUCTE") (field (name "BOM_Supplier Part") "C159867"))
      (libsource (lib "") (part "RCUCTE"))
    )
    (comp (ref "U1")
      (value "LT3042")
      (fields
        (field (name "BOM_Manufacturer Part") "LT3042EMSE#PBF")
        (field (name "BOM_Supplier Part") "C69847")
      )
      (libsource (lib "") (part "LT3042EMSE#PBF"))
    )
    (comp (ref "U9") (value "PicoDIV") (libsource (lib "") (part "Pico")))
    (comp (ref "U11")
      (value "BUF602")
      (fields
        (field (name "BOM_Manufacturer Part") "BUF602IDBVR")
        (field (name "BOM_Supplier Part") "C2060701")
      )
      (libsource (lib "") (part "BUF602IDBVR"))
    )
    (comp (ref "C24")
      (value "10nF")
      (fields
        (field (name "BOM_Manufacturer Part") "CL21B103KBANNNC")
        (field (name "BOM_Supplier Part") "C1710")
      )
      (libsource (lib "") (part "CL21B103KBANNNC"))
    )
    (comp (ref "C25")
      (value "33pF")
      (fields
        (field (name "BOM_Manufacturer Part") "CL21C330JBANNNC")
        (field (name "BOM_Supplier Part") "C1814")
      )
      (libsource (lib "") (part "CL21C330JBANNNC"))
    )
    (comp (ref "C28")
      (value "470pF")
      (fields
        (field (name "BOM_Manufacturer Part") "CL21C471JBANNNC")
        (field (name "BOM_Supplier Part") "C28256")
      )
      (libsource (lib "") (part "CL21C471JBANNNC"))
    )
    (comp (ref "C29")
      (value "100nF")
      (fields
        (field (name "BOM_Manufacturer Part") "CC0805KRX7R9BB104")
        (field (name "BOM_Supplier Part") "C49678")
      )
      (libsource (lib "") (part "CC0805KRX7R9BB104"))
    )
    (comp (ref "C30")
      (value "22uF")
      (fields
        (field (name "BOM_Manufacturer Part") "CL21A226MPQNNNE")
        (field (name "BOM_Supplier Part") "C29277")
      )
      (libsource (lib "") (part "CL21A226MPQNNNE"))
    )
    (comp (ref "C32")
      (value "100nF")
      (fields
        (field (name "BOM_Manufacturer Part") "CC0805KRX7R9BB104")
        (field (name "BOM_Supplier Part") "C49678")
      )
      (libsource (lib "") (part "CC0805KRX7R9BB104_1"))
    )
    (comp (ref "C34")
      (value "10nF")
      (fields
        (field (name "BOM_Manufacturer Part") "CL21B103KBANNNC")
        (field (name "BOM_Supplier Part") "C1710")
      )
      (libsource (lib "") (part "CL21B103KBANNNC"))
    )
    (comp (ref "D12")
      (value "SMCJ43CA")
      (fields (field (name "BOM_Supplier Part") "C310053"))
      (libsource (lib "") (part "SMCJ43CA"))
    )
    (comp (ref "D13")
      (value "BAV99WT1G")
      (fields (field (name "BOM_Supplier Part") "C82078"))
      (libsource (lib "") (part "BAV99WT1G"))
    )
    (comp (ref "D15")
      (value "BZX84C3V3")
      (fields
        (field (name "BOM_Manufacturer Part") "SZBZX84C3V3LT1G")
        (field (name "BOM_Supplier Part") "C231240")
      )
      (libsource (lib "") (part "SZBZX84C3V3LT1G"))
    )
    (comp (ref "EXTCLK")
      (value "ChA")
      (fields
        (field (name "BOM_Manufacturer Part") "KH-IPEX-K501-29")
        (field (name "BOM_Supplier Part") "C411563")
      )
      (libsource (lib "") (part "KH-IPEX-K501-29"))
    )
    (comp (ref "P2")
      (value "TLV3501")
      (fields
        (field (name "BOM_Manufacturer Part") "TLV3501AIDR")
        (field (name "BOM_Supplier Part") "C43484")
      )
      (libsource (lib "") (part "TLV3501AIDR"))
    )
    (comp (ref "R34")
      (value "0")
      (fields
        (field (name "BOM_Manufacturer Part") "0805W8F0000T5E")
        (field (name "BOM_Supplier Part") "C17477")
      )
      (libsource (lib "") (part "0805W8F0000T5E"))
    )
    (comp (ref "R39")
      (value "49.9")
      (fields
        (field (name "BOM_Manufacturer Part") "0805W8F499JT5E")
        (field (name "BOM_Supplier Part") "C17720")
      )
      (libsource (lib "") (part "0805W8F499JT5E"))
    )
    (comp (ref "R40")
      (value "0")
      (fields
        (field (name "BOM_Manufacturer Part") "0805W8F0000T5E")
        (field (name "BOM_Supplier Part") "C17477")
      )
      (libsource (lib "") (part "0805W8F0000T5E"))
    )
    (comp (ref "R41")
      (value "0")
      (fields
        (field (name "BOM_Manufacturer Part") "0805W8F0000T5E")
        (field (name "BOM_Supplier Part") "C17477")
      )
      (libsource (lib "") (part "0805W8F0000T5E_2"))
    )
    (comp (ref "R42")
      (value "0")
      (fields
        (field (name "BOM_Manufacturer Part") "0805W8F0000T5E")
        (field (name "BOM_Supplier Part") "C17477")
      )
      (libsource (lib "") (part "0805W8F0000T5E_1"))
    )
    (comp (ref "R43")
      (value "10k")
      (fields
        (field (name "BOM_Manufacturer Part") "0805W8F1002T5E")
        (field (name "BOM_Supplier Part") "C17414")
      )
      (libsource (lib "") (part "0805W8F1000T5E"))
    )
    (comp (ref "R44")
      (value "100K")
      (fields
        (field (name "BOM_Manufacturer Part") "0805W8F1003T5E")
        (field (name "BOM_Supplier Part") "C17407")
      )
      (libsource (lib "") (part "0805W8F1003T5E"))
    )
    (comp (ref "R45")
      (value "2.15K")
      (fields
        (field (name "BOM_Manufacturer Part") "0805W8F2151T5E")
        (field (name "BOM_Supplier Part") "C17516")
      )
      (libsource (lib "") (part "0805W8F2151T5E"))
    )
    (comp (ref "R46")
      (value "1K")
      (fields
        (field (name "BOM_Manufacturer Part") "0805W8F1001T5E")
        (field (name "BOM_Supplier Part") "C17513")
      )
      (libsource (lib "") (part "0805W8F1001T5E"))
    )
    (comp (ref "R47")
      (value "100K")
      (fields
        (field (name "BOM_Manufacturer Part") "0805W8F1003T5E")
        (field (name "BOM_Supplier Part") "C17407")
      )
      (libsource (lib "") (part "0805W8F1003T5E"))
    )
    (comp (ref "R48")
      (value "100")
      (fields
        (field (name "BOM_Manufacturer Part") "0805W8F1000T5E")
        (field (name "BOM_Supplier Part") "C17408")
      )
      (libsource (lib "") (part "0805W8F1000T5E_1"))
    )
    (comp (ref "R49")
      (value "33K")
      (fields
        (field (name "BOM_Manufacturer Part") "0805W8F3302T5E")
        (field (name "BOM_Supplier Part") "C17633")
      )
      (libsource (lib "") (part "0805W8F1003T5E"))
    )
    (comp (ref "R50")
      (value "10K")
      (fields
        (field (name "BOM_Manufacturer Part") "0805W8F1002T5E")
        (field (name "BOM_Supplier Part") "C17414")
      )
      (libsource (lib "") (part "0805W8F1002T5E"))
    )
    (comp (ref "R51")
      (value "33K")
      (fields
        (field (name "BOM_Manufacturer Part") "0805W8F3302T5E")
        (field (name "BOM_Supplier Part") "C17633")
      )
      (libsource (lib "") (part "0805W8F1003T5E"))
    )
    (comp (ref "RF3")
      (value "KH-SMA-KE8-G")
      (fields (field (name "BOM_Supplier Part") "C530661"))
      (libsource (lib "") (part "KH-SMA-KE8-G"))
    )
    (comp (ref "T4")
      (value "PWB1040")
      (fields
        (field (name "BOM_Manufacturer Part") "PE-68386NLT")
        (field (name "BOM_Supplier Part") "C581397")
      )
      (libsource (lib "") (part "PWB1040 COILCRAFT"))
    )
    (comp (ref "TP4")
      (value "CLK")
      (fields (field (name "BOM_Manufacturer Part") "RCUCTE") (field (name "BOM_Supplier Part") "C159867"))
      (libsource (lib "") (part "RCUCTE"))
    )
    (comp (ref "U12")
      (value "SN74LVC1G17DBVR")
      (fields (field (name "BOM_Supplier Part") "C7836"))
      (libsource (lib "") (part "SN74LVC1G17DBVR"))
    )
    (comp (ref "U13")
      (value "NB3L553")
      (fields
        (field (name "BOM_Manufacturer Part") "NB3L553DR2G")
        (field (name "BOM_Supplier Part") "C145512")
      )
      (libsource (lib "") (part "NB3L553DR2G"))
    )
    (comp (ref "U16")
      (value "ADG836")
      (fields
        (field (name "BOM_Manufacturer Part") "ADG836YRMZ")
        (field (name "BOM_Supplier Part") "C208153")
      )
      (libsource (lib "") (part "ADG836YRMZ"))
    )
  )
  (nets
    (net (code "1") (name "3.3V") (class "Default")
      (node (ref "C15") (pin "2") (pinfunction "2_2") (pintype "input"))
      (node (ref "C16") (pin "1") (pinfunction "1_1") (pintype "input"))
      (node (ref "C17") (pin "1") (pinfunction "1_1") (pintype "input"))
      (node (ref "C24") (pin "1") (pinfunction "1_1") (pintype "input"))
      (node (ref "C3") (pin "1") (pinfunction "1_1") (pintype "input"))
      (node (ref "C32") (pin "1") (pinfunction "1_1") (pintype "input"))
      (node (ref "C6") (pin "2") (pinfunction "2_2") (pintype "input"))
      (node (ref "C7") (pin "2") (pinfunction "2_2") (pintype "input"))
      (node (ref "C8") (pin "2") (pinfunction "2_2") (pintype "unspecified"))
      (node (ref "C9") (pin "2") (pinfunction "2_2") (pintype "unspecified"))
      (node (ref "R15") (pin "2") (pinfunction "2_2") (pintype "input"))
      (node (ref "R21") (pin "1") (pinfunction "1_1") (pintype "input"))
      (node (ref "R29") (pin "2") (pinfunction "2_2") (pintype "input"))
      (node (ref "R38") (pin "2") (pinfunction "2_2") (pintype "input"))
      (node (ref "R41") (pin "2") (pinfunction "2_2") (pintype "input"))
      (node (ref "R46") (pin "2") (pinfunction "2_2") (pintype "input"))
      (node (ref "R7") (pin "2") (pinfunction "2_2") (pintype "input"))
      (node (ref "TP3") (pin "1") (pinfunction "1_1") (pintype "unspecified"))
      (node (ref "U1") (pin "10") (pinfunction "OUT_10") (pintype "unspecified"))
      (node (ref "U1") (pin "9") (pinfunction "OUTS_9") (pintype "unspecified"))
      (node (ref "U10") (pin "1") (pinfunction "VDD_1") (pintype "unspecified"))
      (node (ref "U10") (pin "8") (pinfunction "OE_8") (pintype "unspecified"))
      (node (ref "U12") (pin "2") (pinfunction "A_2") (pintype "unspecified"))
      (node (ref "U12") (pin "5") (pinfunction "VCC_5") (pintype "unspecified"))
      (node (ref "U13") (pin "1") (pinfunction "VDD_1") (pintype "unspecified"))
      (node (ref "U13") (pin "8") (pinfunction "OE_8") (pintype "unspecified"))
      (node (ref "U16") (pin "8") (pinfunction "VDD_8") (pintype "passive"))
      (node (ref "U3") (pin "2") (pinfunction "A_2") (pintype "unspecified"))
      (node (ref "U3") (pin "5") (pinfunction "VCC_5") (pintype "unspecified"))
      (node (ref "U4") (pin "5") (pinfunction "EN_5") (pintype "unspecified"))
      (node (ref "U4") (pin "6") (pinfunction "V+_6") (pintype "unspecified"))
      (node (ref "U5") (pin "5") (pinfunction "EN_5") (pintype "unspecified"))
      (node (ref "U5") (pin "6") (pinfunction "V+_6") (pintype "unspecified"))
      (node (ref "U7") (pin "1") (pinfunction "VDD_1") (pintype "unspecified"))
      (node (ref "U7") (pin "8") (pinfunction "OE_8") (pintype "unspecified"))
      (node (ref "U8") (pin "14") (pinfunction "VDD_14") (pintype "unspecified"))
    )
    (net (code "2") (name "3V3") (class "Default")
      (node (ref "C10") (pin "1") (pinfunction "1_1") (pintype "input"))
      (node (ref "R53") (pin "1") (pinfunction "1_1") (pintype "input"))
      (node (ref "U6") (pin "8") (pinfunction "VDD_8") (pintype "passive"))
      (node (ref "U9") (pin "36") (pinfunction "3V3_36") (pintype "unspecified"))
    )
    (net (code "3") (name "5V0") (class "Default")
      (node (ref "C13") (pin "2") (pinfunction "2_2") (pintype "input"))
      (node (ref "P1") (pin "26") (pinfunction "26_26") (pintype "unspecified"))
      (node (ref "P1") (pin "28") (pinfunction "28_28") (pintype "unspecified"))
      (node (ref "Q2") (pin "3") (pinfunction "D_3") (pintype "unspecified"))
      (node (ref "R22") (pin "2") (pinfunction "2_2") (pintype "input"))
      (node (ref "R52") (pin "1") (pinfunction "1_1") (pintype "input"))
      (node (ref "U1") (pin "1") (pinfunction "IN_1") (pintype "unspecified"))
      (node (ref "U1") (pin "2") (pinfunction "IN_2") (pintype "unspecified"))
      (node (ref "U1") (pin "3") (pinfunction "EN/UV_3") (pintype "unspecified"))
    )
    (net (code "4") (name "CLK") (class "Default")
      (node (ref "U13") (pin "2") (pinfunction "Q0_2") (pintype "unspecified"))
      (node (ref "U4") (pin "9") (pinfunction "NO2_9") (pintype "unspecified"))
      (node (ref "U5") (pin "7") (pinfunction "NO4_7") (pintype "unspecified"))
      (node (ref "U8") (pin "5") (pinfunction "CLOCK_5") (pintype "unspecified"))
    )
    (net (code "5") (name "CLKPico") (class "Default")
      (node (ref "U13") (pin "3") (pinfunction "Q1_3") (pintype "unspecified"))
      (node (ref "U9") (pin "29") (pinfunction "GPIO22_29") (pintype "bidirectional"))
    )
    (net (code "6") (name "CSB") (class "Default")
      (node (ref "P1") (pin "14") (pinfunction "14_14") (pintype "unspecified"))
      (node (ref "U8") (pin "11") (pinfunction "CSB_11") (pintype "unspecified"))
    )
    (net (code "7") (name "Ch1IND") (class "Default")
      (node (ref "P1") (pin "6") (pinfunction "6_6") (pintype "unspecified"))
      (node (ref "U7") (pin "6") (pinfunction "Q2_6") (pintype "unspecified"))
    )
    (net (code "8") (name "Ch1START") (class "Default")
      (node (ref "U4") (pin "2") (pinfunction "NO1_2") (pintype "unspecified"))
      (node (ref "U7") (pin "3") (pinfunction "Q1_3") (pintype "unspecified"))
    )
    (net (code "9") (name "Ch1STOP") (class "Default")
      (node (ref "U5") (pin "2") (pinfunction "NO1_2") (pintype "unspecified"))
      (node (ref "U7") (pin "2") (pinfunction "Q0_2") (pintype "unspecified"))
    )
    (net (code "10") (name "Ch1_50Imp") (class "Default")
      (node (ref "U6") (pin "1") (pinfunction "IN1_1") (pintype "unspecified"))
      (node (ref "U9") (pin "15") (pinfunction "GPIO11_15") (pintype "bidirectional"))
    )
    (net (code "11") (name "Ch2IND") (class "Default")
      (node (ref "P1") (pin "4") (pinfunction "4_4") (pintype "unspecified"))
      (node (ref "U10") (pin "7") (pinfunction "Q3_7") (pintype "unspecified"))
    )
    (net (code "12") (name "Ch2START") (class "Default")
      (node (ref "U10") (pin "2") (pinfunction "Q0_2") (pintype "unspecified"))
      (node (ref "U4") (pin "4") (pinfunction "NO3_4") (pintype "unspecified"))
    )
    (net (code "13") (name "Ch2STOP") (class "Default")
      (node (ref "U10") (pin "3") (pinfunction "Q1_3") (pintype "unspecified"))
      (node (ref "U5") (pin "4") (pinfunction "NO3_4") (pintype "unspecified"))
    )
    (net (code "14") (name "Ch2_50Imp") (class "Default")
      (node (ref "U6") (pin "5") (pinfunction "IN2_5") (pintype "unspecified"))
      (node (ref "U9") (pin "14") (pinfunction "GPIO10_14") (pintype "bidirectional"))
    )
    (net (code "15") (name "ClkIND") (class "Default")
      (node (ref "P1") (pin "1") (pinfunction "1_1") (pintype "unspecified"))
      (node (ref "U13") (pin "7") (pinfunction "Q3_7") (pintype "unspecified"))
    )
    (net (code "16") (name "DGND") (class "Default")
      (node (ref "C11") (pin "2") (pinfunction "2_2") (pintype "input"))
      (node (ref "C12") (pin "1") (pinfunction "1_1") (pintype "input"))
      (node (ref "C16") (pin "2") (pinfunction "2_2") (pintype "input"))
      (node (ref "C17") (pin "2") (pinfunction "2_2") (pintype "input"))
      (node (ref "C18") (pin "2") (pinfunction "2_2") (pintype "input"))
      (node (ref "C2") (pin "1") (pinfunction "1_1") (pintype "input"))
      (node (ref "C22") (pin "1") (pinfunction "1_1") (pintype "input"))
      (node (ref "C23") (pin "1") (pinfunction "1_1") (pintype "input"))
      (node (ref "C24") (pin "2") (pinfunction "2_2") (pintype "input"))
      (node (ref "C25") (pin "2") (pinfunction "2_2") (pintype "input"))
      (node (ref "C26") (pin "1") (pinfunction "1_1") (pintype "input"))
      (node (ref "C27") (pin "1") (pinfunction "1_1") (pintype "input"))
      (node (ref "C29") (pin "1") (pinfunction "1_1") (pintype "input"))
      (node (ref "C3") (pin "2") (pinfunction "2_2") (pintype "input"))
      (node (ref "C30") (pin "1") (pinfunction "1_1") (pintype "input"))
      (node (ref "C31") (pin "2") (pinfunction "2_2") (pintype "input"))
      (node (ref "C32") (pin "2") (pinfunction "2_2") (pintype "input"))
      (node (ref "C33") (pin "2") (pinfunction "2_2") (pintype "input"))
      (node (ref "C34") (pin "2") (pinfunction "2_2") (pintype "input"))
      (node (ref "C4") (pin "1") (pinfunction "1_1") (pintype "input"))
      (node (ref "C6") (pin "1") (pinfunction "1_1") (pintype "input"))
      (node (ref "C7") (pin "1") (pinfunction "1_1") (pintype "input"))
      (node (ref "C8") (pin "1") (pinfunction "1_1") (pintype "unspecified"))
      (node (ref "C9") (pin "1") (pinfunction "1_1") (pintype "unspecified"))
      (node (ref "D15") (pin "1") (pinfunction "A_1") (pintype "unspecified"))
      (node (ref "D4") (pin "1") (pinfunction "A_1") (pintype "unspecified"))
      (node (ref "D5") (pin "1") (pinfunction "A_1") (pintype "unspecified"))
      (node (ref "P2") (pin "4") (pinfunction "V-_4") (pintype "unspecified"))
      (node (ref "P2") (pin "8") (pinfunction "SHDN_8") (pintype "unspecified"))
      (node (ref "R11") (pin "1") (pinfunction "1_1") (pintype "input"))
      (node (ref "R12") (pin "1") (pinfunction "1_1") (pintype "input"))
      (node (ref "R14") (pin "1") (pinfunction "1_1") (pintype "input"))
      (node (ref "R19") (pin "2") (pinfunction "2_2") (pintype "input"))
      (node (ref "R23") (pin "2") (pinfunction "2_2") (pintype "input"))
      (node (ref "R3") (pin "1") (pinfunction "1_1") (pintype "input"))
      (node (ref "R33") (pin "1") (pinfunction "1_1") (pintype "input"))
      (node (ref "R35") (pin "1") (pinfunction "1_1") (pintype "input"))
      (node (ref "R36") (pin "1") (pinfunction "1_1") (pintype "input"))
      (node (ref "R39") (pin "2") (pinfunction "2_2") (pintype "input"))
      (node (ref "R43") (pin "1") (pinfunction "1_1") (pintype "input"))
      (node (ref "R47") (pin "1") (pinfunction "1_1") (pintype "input"))
      (node (ref "R5") (pin "1") (pinfunction "1_1") (pintype "input"))
      (node (ref "R50") (pin "1") (pinfunction "1_1") (pintype "input"))
      (node (ref "U10") (pin "4") (pinfunction "GND_4") (pintype "unspecified"))
      (node (ref "U12") (pin "3") (pinfunction "GND_3") (pintype "unspecified"))
      (node (ref "U13") (pin "4") (pinfunction "GND_4") (pintype "unspecified"))
      (node (ref "U16") (pin "3") (pinfunction "GND_3") (pintype "passive"))
      (node (ref "U2") (pin "5") (pinfunction "V-_5") (pintype "unspecified"))
      (node (ref "U3") (pin "3") (pinfunction "GND_3") (pintype "unspecified"))
      (node (ref "U4") (pin "3") (pinfunction "GND_3") (pintype "unspecified"))
      (node (ref "U5") (pin "3") (pinfunction "GND_3") (pintype "unspecified"))
      (node (ref "U7") (pin "4") (pinfunction "GND_4") (pintype "unspecified"))
      (node (ref "U8") (pin "7") (pinfunction "GND_7") (pintype "unspecified"))
    )
    (net (code "17") (name "DIN") (class "Default")
      (node (ref "P1") (pin "11") (pinfunction "11_11") (pintype "unspecified"))
      (node (ref "U8") (pin "10") (pinfunction "DIN_10") (pintype "unspecified"))
    )
    (net (code "18") (name "DOUT") (class "Default")
      (node (ref "P1") (pin "12") (pinfunction "12_12") (pintype "unspecified"))
      (node (ref "U8") (pin "9") (pinfunction "DOUT_9") (pintype "unspecified"))
    )
    (net (code "19") (name "DivCLK") (class "Default")
      (node (ref "R30") (pin "1") (pinfunction "1_1") (pintype "input"))
      (node (ref "R32") (pin "2") (pinfunction "2_2") (pintype "input"))
      (node (ref "U9") (pin "22") (pinfunction "GPIO17_22") (pintype "bidirectional"))
    )
    (net (code "20") (name "ExtClkSEL") (class "Default")
      (node (ref "P2") (pin "6") (pinfunction "OUT_6") (pintype "unspecified"))
      (node (ref "U16") (pin "2") (pinfunction "S1A_2") (pintype "unspecified"))
    )
    (net (code "21") (name "GND") (class "Default")
      (node (ref "C10") (pin "2") (pinfunction "2_2") (pintype "input"))
      (node (ref "C13") (pin "1") (pinfunction "1_1") (pintype "input"))
      (node (ref "C14") (pin "1") (pinfunction "1_1") (pintype "input"))
      (node (ref "C15") (pin "1") (pinfunction "1_1") (pintype "input"))
      (node (ref "C19") (pin "2") (pinfunction "2_2") (pintype "input"))
      (node (ref "C20") (pin "2") (pinfunction "2_2") (pintype "input"))
      (node (ref "C21") (pin "1") (pinfunction "1_1") (pintype "input"))
      (node (ref "C22") (pin "2") (pinfunction "2_2") (pintype "input"))
      (node (ref "C23") (pin "2") (pinfunction "2_2") (pintype "input"))
      (node (ref "C26") (pin "2") (pinfunction "2_2") (pintype "input"))
      (node (ref "C27") (pin "2") (pinfunction "2_2") (pintype "input"))
      (node (ref "D1") (pin "2") (pinfunction "A_2") (pintype "input"))
      (node (ref "D12") (pin "2") (pinfunction "A_2") (pintype "input"))
      (node (ref "D8") (pin "2") (pinfunction "A_2") (pintype "input"))
      (node (ref "DIVCLK") (pin "1") (pinfunction "GND_1") (pintype "unspecified"))
      (node (ref "DIVCLK") (pin "3") (pinfunction "GND_3") (pintype "unspecified"))
      (node (ref "P1") (pin "15") (pinfunction "15_15") (pintype "unspecified"))
      (node (ref "P1") (pin "16") (pinfunction "16_16") (pintype "unspecified"))
      (node (ref "P1") (pin "18") (pinfunction "18_18") (pintype "unspecified"))
      (node (ref "P1") (pin "24") (pinfunction "24_24") (pintype "unspecified"))
      (node (ref "P1") (pin "25") (pinfunction "25_25") (pintype "unspecified"))
      (node (ref "P1") (pin "27") (pinfunction "27_27") (pintype "unspecified"))
      (node (ref "P1") (pin "3") (pinfunction "3_3") (pintype "unspecified"))
      (node (ref "P1") (pin "8") (pinfunction "8_8") (pintype "unspecified"))
      (node (ref "R26") (pin "2") (pinfunction "2_2") (pintype "input"))
      (node (ref "R27") (pin "1") (pinfunction "1_1") (pintype "input"))
      (node (ref "R28") (pin "1") (pinfunction "1_1") (pintype "input"))
      (node (ref "R32") (pin "1") (pinfunction "1_1") (pintype "input"))
      (node (ref "R33") (pin "2") (pinfunction "2_2") (pintype "input"))
      (node (ref "R35") (pin "2") (pinfunction "2_2") (pintype "input"))
      (node (ref "R36") (pin "2") (pinfunction "2_2") (pintype "input"))
      (node (ref "R44") (pin "1") (pinfunction "1_1") (pintype "input"))
      (node (ref "RF4") (pin "1") (pinfunction "1_1") (pintype "unspecified"))
      (node (ref "RF4") (pin "2") (pinfunction "2_2") (pintype "unspecified"))
      (node (ref "RF4") (pin "3") (pinfunction "3_3") (pintype "unspecified"))
      (node (ref "RF4") (pin "4") (pinfunction "4_4") (pintype "unspecified"))
      (node (ref "U1") (pin "11") (pinfunction "GND_11") (pintype "unspecified"))
      (node (ref "U1") (pin "8") (pinfunction "GND_8") (pintype "unspecified"))
      (node (ref "U11") (pin "2") (pinfunction "−VCC_2") (pintype "unspecified"))
      (node (ref "U6") (pin "10") (pinfunction "D1_10") (pintype "unspecified"))
      (node (ref "U6") (pin "3") (pinfunction "GND_3") (pintype "passive"))
      (node (ref "U6") (pin "6") (pinfunction "D2_6") (pintype "unspecified"))
      (node (ref "U9") (pin "13") (pinfunction "GND_13") (pintype "bidirectional"))
      (node (ref "U9") (pin "18") (pinfunction "GND_18") (pintype "bidirectional"))
      (node (ref "U9") (pin "23") (pinfunction "GND_23") (pintype "bidirectional"))
      (node (ref "U9") (pin "28") (pinfunction "GND_28") (pintype "bidirectional"))
      (node (ref "U9") (pin "3") (pinfunction "GND_3") (pintype "bidirectional"))
      (node (ref "U9") (pin "38") (pinfunction "GND_38") (pintype "bidirectional"))
      (node (ref "U9") (pin "8") (pinfunction "GND_8") (pintype "bidirectional"))
    )
    (net (code "22") (name "INTB") (class "Default")
      (node (ref "P1") (pin "10") (pinfunction "10_10") (pintype "unspecified"))
      (node (ref "U8") (pin "8") (pinfunction "INTB_8") (pintype "unspecified"))
    )
    (net (code "23") (name "IntCLK") (class "Default")
      (node (ref "P1") (pin "2") (pinfunction "2_2") (pintype "unspecified"))
      (node (ref "U16") (pin "9") (pinfunction "S1B_9") (pintype "unspecified"))
    )
    (net (code "24") (name "Net-(C1-Pad2)") (class "Default")
      (node (ref "C1") (pin "2") (pinfunction "2_2") (pintype "input"))
      (node (ref "R2") (pin "2") (pinfunction "2_2") (pintype "input"))
      (node (ref "T1") (pin "1") (pinfunction "1_1") (pintype "unspecified"))
    )
    (net (code "25") (name "Net-(C5-Pad2)") (class "Default")
      (node (ref "C5") (pin "2") (pinfunction "2_2") (pintype "input"))
      (node (ref "R20") (pin "2") (pinfunction "2_2") (pintype "input"))
      (node (ref "T2") (pin "1") (pinfunction "1_1") (pintype "unspecified"))
    )
    (net (code "26") (name "Net-(C28-Pad2)") (class "Default")
      (node (ref "C28") (pin "2") (pinfunction "2_2") (pintype "input"))
      (node (ref "R45") (pin "2") (pinfunction "2_2") (pintype "input"))
      (node (ref "T4") (pin "1") (pinfunction "1_1") (pintype "unspecified"))
    )
    (net (code "27") (name "Net-(C31-Pad1)") (class "Default")
      (node (ref "C31") (pin "1") (pinfunction "1_1") (pintype "input"))
      (node (ref "T1") (pin "4") (pinfunction "4_4") (pintype "unspecified"))
    )
    (net (code "28") (name "Net-(C33-Pad1)") (class "Default")
      (node (ref "C33") (pin "1") (pinfunction "1_1") (pintype "input"))
      (node (ref "T2") (pin "4") (pinfunction "4_4") (pintype "unspecified"))
    )
    (net (code "29") (name "Net-(C34-Pad1)") (class "Default")
      (node (ref "C34") (pin "1") (pinfunction "1_1") (pintype "input"))
      (node (ref "T4") (pin "4") (pinfunction "4_4") (pintype "unspecified"))
    )
    (net (code "30") (name "Net-(CH1-CONT)") (class "Default")
      (node (ref "C1") (pin "1") (pinfunction "1_1") (pintype "input"))
      (node (ref "CH1") (pin "2") (pinfunction "CONT_2") (pintype "unspecified"))
      (node (ref "RF1") (pin "5") (pinfunction "5_5") (pintype "unspecified"))
    )
    (net (code "31") (name "Net-(CH2-CONT)") (class "Default")
      (node (ref "C5") (pin "1") (pinfunction "1_1") (pintype "input"))
      (node (ref "CH2") (pin "2") (pinfunction "CONT_2") (pintype "unspecified"))
      (node (ref "RF2") (pin "5") (pinfunction "5_5") (pintype "unspecified"))
    )
    (net (code "32") (name "Net-(D1-K)") (class "Default")
      (node (ref "CH1") (pin "1") (pinfunction "SGND_1") (pintype "unspecified"))
      (node (ref "CH1") (pin "3") (pinfunction "SGND_3") (pintype "unspecified"))
      (node (ref "D1") (pin "1") (pinfunction "K_1") (pintype "input"))
      (node (ref "R1") (pin "2") (pinfunction "2_2") (pintype "input"))
      (node (ref "R2") (pin "1") (pinfunction "1_1") (pintype "input"))
      (node (ref "R4") (pin "1") (pinfunction "1_1") (pintype "input"))
      (node (ref "RF1") (pin "1") (pinfunction "1_1") (pintype "unspecified"))
      (node (ref "RF1") (pin "2") (pinfunction "2_2") (pintype "unspecified"))
      (node (ref "RF1") (pin "3") (pinfunction "3_3") (pintype "unspecified"))
      (node (ref "RF1") (pin "4") (pinfunction "4_4") (pintype "unspecified"))
      (node (ref "T1") (pin "3") (pinfunction "3_3") (pintype "unspecified"))
    )
    (net (code "33") (name "Net-(D3-A)") (class "Default")
      (node (ref "D3") (pin "1") (pinfunction "A_1") (pintype "unspecified"))
      (node (ref "R5") (pin "2") (pinfunction "2_2") (pintype "input"))
    )
    (net (code "34") (name "Net-(D3-A{slash}C)") (class "Default")
      (node (ref "D3") (pin "3") (pinfunction "A/C_3") (pintype "unspecified"))
      (node (ref "D4") (pin "3") (pinfunction "K_3") (pintype "unspecified"))
      (node (ref "R12") (pin "2") (pinfunction "2_2") (pintype "input"))
      (node (ref "R9") (pin "1") (pinfunction "1_1") (pintype "input"))
      (node (ref "T1") (pin "6") (pinfunction "6_6") (pintype "unspecified"))
    )
    (net (code "35") (name "Net-(D3-C)") (class "Default")
      (node (ref "D3") (pin "2") (pinfunction "C_2") (pintype "unspecified"))
      (node (ref "R7") (pin "1") (pinfunction "1_1") (pintype "input"))
    )
    (net (code "36") (name "Net-(D5-K)") (class "Default")
      (node (ref "D5") (pin "3") (pinfunction "K_3") (pintype "unspecified"))
      (node (ref "D7") (pin "3") (pinfunction "A/C_3") (pintype "unspecified"))
      (node (ref "R13") (pin "1") (pinfunction "1_1") (pintype "input"))
      (node (ref "R3") (pin "2") (pinfunction "2_2") (pintype "input"))
      (node (ref "T2") (pin "6") (pinfunction "6_6") (pintype "unspecified"))
    )
    (net (code "37") (name "Net-(D7-A)") (class "Default")
      (node (ref "D7") (pin "1") (pinfunction "A_1") (pintype "unspecified"))
      (node (ref "R14") (pin "2") (pinfunction "2_2") (pintype "input"))
    )
    (net (code "38") (name "Net-(D7-C)") (class "Default")
      (node (ref "D7") (pin "2") (pinfunction "C_2") (pintype "unspecified"))
      (node (ref "R15") (pin "1") (pinfunction "1_1") (pintype "input"))
    )
    (net (code "39") (name "Net-(D8-K)") (class "Default")
      (node (ref "CH2") (pin "1") (pinfunction "SGND_1") (pintype "unspecified"))
      (node (ref "CH2") (pin "3") (pinfunction "SGND_3") (pintype "unspecified"))
      (node (ref "D8") (pin "1") (pinfunction "K_1") (pintype "input"))
      (node (ref "R16") (pin "2") (pinfunction "2_2") (pintype "input"))
      (node (ref "R17") (pin "1") (pinfunction "1_1") (pintype "input"))
      (node (ref "R20") (pin "1") (pinfunction "1_1") (pintype "input"))
      (node (ref "RF2") (pin "1") (pinfunction "1_1") (pintype "unspecified"))
      (node (ref "RF2") (pin "2") (pinfunction "2_2") (pintype "unspecified"))
      (node (ref "RF2") (pin "3") (pinfunction "3_3") (pintype "unspecified"))
      (node (ref "RF2") (pin "4") (pinfunction "4_4") (pintype "unspecified"))
      (node (ref "T2") (pin "3") (pinfunction "3_3") (pintype "unspecified"))
    )
    (net (code "40") (name "Net-(D12-K)") (class "Default")
      (node (ref "D12") (pin "1") (pinfunction "K_1") (pintype "input"))
      (node (ref "EXTCLK") (pin "1") (pinfunction "SGND_1") (pintype "unspecified"))
      (node (ref "EXTCLK") (pin "3") (pinfunction "SGND_3") (pintype "unspecified"))
      (node (ref "R44") (pin "2") (pinfunction "2_2") (pintype "input"))
      (node (ref "R45") (pin "1") (pinfunction "1_1") (pintype "input"))
      (node (ref "RF3") (pin "1") (pinfunction "1_1") (pintype "unspecified"))
      (node (ref "RF3") (pin "2") (pinfunction "2_2") (pintype "unspecified"))
      (node (ref "RF3") (pin "3") (pinfunction "3_3") (pintype "unspecified"))
      (node (ref "RF3") (pin "4") (pinfunction "4_4") (pintype "unspecified"))
      (node (ref "T4") (pin "3") (pinfunction "3_3") (pintype "unspecified"))
    )
    (net (code "41") (name "Net-(D13-A)") (class "Default")
      (node (ref "D13") (pin "1") (pinfunction "A_1") (pintype "unspecified"))
      (node (ref "R47") (pin "2") (pinfunction "2_2") (pintype "input"))
    )
    (net (code "42") (name "Net-(D13-A{slash}C)") (class "Default")
      (node (ref "D13") (pin "3") (pinfunction "A/C_3") (pintype "unspecified"))
      (node (ref "D15") (pin "3") (pinfunction "K_3") (pintype "unspecified"))
      (node (ref "R48") (pin "1") (pinfunction "1_1") (pintype "input"))
      (node (ref "R50") (pin "2") (pinfunction "2_2") (pintype "input"))
      (node (ref "T4") (pin "6") (pinfunction "6_6") (pintype "unspecified"))
    )
    (net (code "43") (name "Net-(D13-C)") (class "Default")
      (node (ref "D13") (pin "2") (pinfunction "C_2") (pintype "unspecified"))
      (node (ref "R46") (pin "1") (pinfunction "1_1") (pintype "input"))
    )
    (net (code "44") (name "Net-(DIVCLK-CONT)") (class "Default")
      (node (ref "DIVCLK") (pin "2") (pinfunction "CONT_2") (pintype "unspecified"))
      (node (ref "R25") (pin "1") (pinfunction "1_1") (pintype "input"))
      (node (ref "RF4") (pin "5") (pinfunction "5_5") (pintype "unspecified"))
    )
    (net (code "45") (name "Net-(EXTCLK-CONT)") (class "Default")
      (node (ref "C28") (pin "1") (pinfunction "1_1") (pintype "input"))
      (node (ref "EXTCLK") (pin "2") (pinfunction "CONT_2") (pintype "unspecified"))
      (node (ref "RF3") (pin "5") (pinfunction "5_5") (pintype "unspecified"))
    )
    (net (code "46") (name "Net-(P2-+IN)") (class "Default")
      (node (ref "P2") (pin "3") (pinfunction "+IN_3") (pintype "unspecified"))
      (node (ref "R48") (pin "2") (pinfunction "2_2") (pintype "input"))
      (node (ref "R49") (pin "1") (pinfunction "1_1") (pintype "input"))
    )
    (net (code "47") (name "Net-(P2--IN)") (class "Default")
      (node (ref "P2") (pin "2") (pinfunction "-IN_2") (pintype "unspecified"))
      (node (ref "R43") (pin "2") (pinfunction "2_2") (pintype "input"))
      (node (ref "R51") (pin "1") (pinfunction "1_1") (pintype "input"))
    )
    (net (code "48") (name "Net-(P2-V+)") (class "Default")
      (node (ref "C29") (pin "2") (pinfunction "2_2") (pintype "input"))
      (node (ref "C30") (pin "2") (pinfunction "2_2") (pintype "input"))
      (node (ref "P2") (pin "7") (pinfunction "V+_7") (pintype "unspecified"))
      (node (ref "R42") (pin "1") (pinfunction "1_1") (pintype "input"))
      (node (ref "U12") (pin "4") (pinfunction "Y_4") (pintype "unspecified"))
    )
    (net (code "49") (name "Net-(Q2-G)") (class "Default")
      (node (ref "Q2") (pin "1") (pinfunction "G_1") (pintype "unspecified"))
      (node (ref "U9") (pin "40") (pinfunction "VBUS_40") (pintype "unspecified"))
    )
    (net (code "50") (name "Net-(Q2-S)") (class "Default")
      (node (ref "Q2") (pin "2") (pinfunction "S_2") (pintype "unspecified"))
      (node (ref "U9") (pin "39") (pinfunction "VSYS_39") (pintype "unspecified"))
    )
    (net (code "51") (name "Net-(R10-Pad2)") (class "Default")
      (node (ref "R10") (pin "2") (pinfunction "2_2") (pintype "input"))
      (node (ref "R37") (pin "2") (pinfunction "2_2") (pintype "input"))
      (node (ref "R38") (pin "1") (pinfunction "1_1") (pintype "input"))
      (node (ref "R6") (pin "1") (pinfunction "1_1") (pintype "input"))
      (node (ref "R8") (pin "2") (pinfunction "2_2") (pintype "input"))
    )
    (net (code "52") (name "Net-(R41-Pad1)") (class "Default")
      (node (ref "R41") (pin "1") (pinfunction "1_1") (pintype "input"))
      (node (ref "R42") (pin "2") (pinfunction "2_2") (pintype "input"))
      (node (ref "R49") (pin "2") (pinfunction "2_2") (pintype "input"))
      (node (ref "R51") (pin "2") (pinfunction "2_2") (pintype "input"))
    )
    (net (code "53") (name "Net-(U1-ILIM)") (class "Default")
      (node (ref "R26") (pin "1") (pinfunction "1_1") (pintype "input"))
      (node (ref "U1") (pin "5") (pinfunction "ILIM_5") (pintype "unspecified"))
    )
    (net (code "54") (name "Net-(U1-PG)") (class "Default")
      (node (ref "R22") (pin "1") (pinfunction "1_1") (pintype "input"))
      (node (ref "U1") (pin "4") (pinfunction "PG_4") (pintype "unspecified"))
    )
    (net (code "55") (name "Net-(U1-PGFB)") (class "Default")
      (node (ref "R28") (pin "2") (pinfunction "2_2") (pintype "input"))
      (node (ref "R29") (pin "1") (pinfunction "1_1") (pintype "input"))
      (node (ref "U1") (pin "6") (pinfunction "PGFB_6") (pintype "unspecified"))
    )
    (net (code "56") (name "Net-(U1-SET)") (class "Default")
      (node (ref "C14") (pin "2") (pinfunction "2_2") (pintype "input"))
      (node (ref "R27") (pin "2") (pinfunction "2_2") (pintype "input"))
      (node (ref "U1") (pin "7") (pinfunction "SET_7") (pintype "unspecified"))
    )
    (net (code "57") (name "Net-(U2-+IN{slash}A)") (class "Default")
      (node (ref "R10") (pin "1") (pinfunction "1_1") (pintype "input"))
      (node (ref "R9") (pin "2") (pinfunction "2_2") (pintype "input"))
      (node (ref "U2") (pin "1") (pinfunction "+IN/A_1") (pintype "unspecified"))
    )
    (net (code "58") (name "Net-(U2-+IN{slash}B)") (class "Default")
      (node (ref "R13") (pin "2") (pinfunction "2_2") (pintype "input"))
      (node (ref "R8") (pin "1") (pinfunction "1_1") (pintype "input"))
      (node (ref "U2") (pin "3") (pinfunction "+IN/B_3") (pintype "unspecified"))
    )
    (net (code "59") (name "Net-(U2--IN{slash}A)") (class "Default")
      (node (ref "R11") (pin "2") (pinfunction "2_2") (pintype "input"))
      (node (ref "R37") (pin "1") (pinfunction "1_1") (pintype "input"))
      (node (ref "U2") (pin "2") (pinfunction "-IN/A_2") (pintype "unspecified"))
      (node (ref "U2") (pin "4") (pinfunction "-IN/B_4") (pintype "unspecified"))
    )
    (net (code "60") (name "Net-(U2-OUTA)") (class "Default")
      (node (ref "R18") (pin "2") (pinfunction "2_2") (pintype "input"))
      (node (ref "U2") (pin "7") (pinfunction "OUTA_7") (pintype "unspecified"))
    )
    (net (code "61") (name "Net-(U2-OUTB)") (class "Default")
      (node (ref "R24") (pin "1") (pinfunction "1_1") (pintype "input"))
      (node (ref "U2") (pin "6") (pinfunction "OUTB_6") (pintype "unspecified"))
    )
    (net (code "62") (name "Net-(U2-V+)") (class "Default")
      (node (ref "C12") (pin "2") (pinfunction "2_2") (pintype "input"))
      (node (ref "C2") (pin "2") (pinfunction "2_2") (pintype "input"))
      (node (ref "R6") (pin "2") (pinfunction "2_2") (pintype "input"))
      (node (ref "U2") (pin "8") (pinfunction "V+_8") (pintype "unspecified"))
      (node (ref "U3") (pin "4") (pinfunction "Y_4") (pintype "unspecified"))
    )
    (net (code "63") (name "Net-(U6-S1A)") (class "Default")
      (node (ref "R1") (pin "1") (pinfunction "1_1") (pintype "input"))
      (node (ref "U6") (pin "2") (pinfunction "S1A_2") (pintype "unspecified"))
    )
    (net (code "64") (name "Net-(U6-S1B)") (class "Default")
      (node (ref "R4") (pin "2") (pinfunction "2_2") (pintype "input"))
      (node (ref "U6") (pin "9") (pinfunction "S1B_9") (pintype "unspecified"))
    )
    (net (code "65") (name "Net-(U6-S2A)") (class "Default")
      (node (ref "R16") (pin "1") (pinfunction "1_1") (pintype "input"))
      (node (ref "U6") (pin "4") (pinfunction "S2A_4") (pintype "unspecified"))
    )
    (net (code "66") (name "Net-(U6-S2B)") (class "Default")
      (node (ref "R17") (pin "2") (pinfunction "2_2") (pintype "input"))
      (node (ref "U6") (pin "7") (pinfunction "S2B_7") (pintype "unspecified"))
    )
    (net (code "67") (name "Net-(U7-ICLK)") (class "Default")
      (node (ref "C11") (pin "1") (pinfunction "1_1") (pintype "input"))
      (node (ref "R18") (pin "1") (pinfunction "1_1") (pintype "input"))
      (node (ref "R19") (pin "1") (pinfunction "1_1") (pintype "input"))
      (node (ref "U7") (pin "5") (pinfunction "ICLK_5") (pintype "unspecified"))
    )
    (net (code "68") (name "Net-(U7-Q3)") (class "Default")
      (node (ref "TP1") (pin "1") (pinfunction "1_1") (pintype "unspecified"))
      (node (ref "U7") (pin "7") (pinfunction "Q3_7") (pintype "unspecified"))
    )
    (net (code "69") (name "Net-(U8-ENABLE)") (class "Default")
      (node (ref "R21") (pin "2") (pinfunction "2_2") (pintype "input"))
      (node (ref "U8") (pin "1") (pinfunction "ENABLE_1") (pintype "unspecified"))
    )
    (net (code "70") (name "Net-(U8-VREG)") (class "Default")
      (node (ref "C4") (pin "2") (pinfunction "2_2") (pintype "input"))
      (node (ref "U8") (pin "13") (pinfunction "VREG_13") (pintype "unspecified"))
    )
    (net (code "71") (name "Net-(U10-ICLK)") (class "Default")
      (node (ref "C18") (pin "1") (pinfunction "1_1") (pintype "input"))
      (node (ref "R23") (pin "1") (pinfunction "1_1") (pintype "input"))
      (node (ref "R24") (pin "2") (pinfunction "2_2") (pintype "input"))
      (node (ref "U10") (pin "5") (pinfunction "ICLK_5") (pintype "unspecified"))
    )
    (net (code "72") (name "Net-(U10-Q2)") (class "Default")
      (node (ref "TP2") (pin "1") (pinfunction "1_1") (pintype "unspecified"))
      (node (ref "U10") (pin "6") (pinfunction "Q2_6") (pintype "unspecified"))
    )
    (net (code "73") (name "Net-(U11-+VCC)") (class "Default")
      (node (ref "C19") (pin "1") (pinfunction "1_1") (pintype "input"))
      (node (ref "C20") (pin "1") (pinfunction "1_1") (pintype "input"))
      (node (ref "R52") (pin "2") (pinfunction "2_2") (pintype "input"))
      (node (ref "R53") (pin "2") (pinfunction "2_2") (pintype "input"))
      (node (ref "U11") (pin "5") (pinfunction "+VCC_5") (pintype "unspecified"))
    )
    (net (code "74") (name "Net-(U11-In)") (class "Default")
      (node (ref "R30") (pin "2") (pinfunction "2_2") (pintype "input"))
      (node (ref "R31") (pin "1") (pinfunction "1_1") (pintype "input"))
      (node (ref "U11") (pin "4") (pinfunction "In_4") (pintype "unspecified"))
    )
    (net (code "75") (name "Net-(U11-Out)") (class "Default")
      (node (ref "R25") (pin "2") (pinfunction "2_2") (pintype "input"))
      (node (ref "U11") (pin "1") (pinfunction "Out_1") (pintype "unspecified"))
    )
    (net (code "76") (name "Net-(U11-VREF)") (class "Default")
      (node (ref "C21") (pin "2") (pinfunction "2_2") (pintype "input"))
      (node (ref "R31") (pin "2") (pinfunction "2_2") (pintype "input"))
      (node (ref "U11") (pin "3") (pinfunction "VREF_3") (pintype "unspecified"))
    )
    (net (code "77") (name "Net-(U13-ICLK)") (class "Default")
      (node (ref "C25") (pin "1") (pinfunction "1_1") (pintype "input"))
      (node (ref "R39") (pin "1") (pinfunction "1_1") (pintype "input"))
      (node (ref "R40") (pin "2") (pinfunction "2_2") (pintype "input"))
      (node (ref "U13") (pin "5") (pinfunction "ICLK_5") (pintype "unspecified"))
    )
    (net (code "78") (name "Net-(U13-Q2)") (class "Default")
      (node (ref "TP4") (pin "1") (pinfunction "1_1") (pintype "unspecified"))
      (node (ref "U13") (pin "6") (pinfunction "Q2_6") (pintype "unspecified"))
    )
    (net (code "79") (name "Net-(U16-D2)") (class "Default")
      (node (ref "R40") (pin "1") (pinfunction "1_1") (pintype "input"))
      (node (ref "U16") (pin "6") (pinfunction "D2_6") (pintype "unspecified"))
    )
    (net (code "80") (name "Net-(U16-S2B)") (class "Default")
      (node (ref "R34") (pin "2") (pinfunction "2_2") (pintype "input"))
      (node (ref "U16") (pin "7") (pinfunction "S2B_7") (pintype "unspecified"))
    )
    (net (code "81") (name "PDIVCS") (class "Default")
      (node (ref "P1") (pin "17") (pinfunction "17_17") (pintype "unspecified"))
      (node (ref "U9") (pin "7") (pinfunction "GPIO5_7") (pintype "bidirectional"))
    )
    (net (code "82") (name "PDIVClk") (class "Default")
      (node (ref "P1") (pin "23") (pinfunction "23_23") (pintype "unspecified"))
      (node (ref "U9") (pin "4") (pinfunction "GPIO2_4") (pintype "bidirectional"))
    )
    (net (code "83") (name "PDIVRx") (class "Default")
      (node (ref "P1") (pin "21") (pinfunction "21_21") (pintype "unspecified"))
      (node (ref "U9") (pin "5") (pinfunction "GPIO3_5") (pintype "bidirectional"))
    )
    (net (code "84") (name "PDIVTx") (class "Default")
      (node (ref "P1") (pin "19") (pinfunction "19_19") (pintype "unspecified"))
      (node (ref "U9") (pin "6") (pinfunction "GPIO4_6") (pintype "bidirectional"))
    )
    (net (code "85") (name "PPSSync") (class "Default")
      (node (ref "P1") (pin "22") (pinfunction "22_22") (pintype "unspecified"))
      (node (ref "U9") (pin "32") (pinfunction "GPIO27_ADC1_32") (pintype "bidirectional"))
    )
    (net (code "86") (name "PicoTCXO") (class "Default")
      (node (ref "R34") (pin "1") (pinfunction "1_1") (pintype "input"))
      (node (ref "U9") (pin "27") (pinfunction "GPIO21_27") (pintype "bidirectional"))
    )
    (net (code "87") (name "RefCLK") (class "Default")
      (node (ref "P1") (pin "20") (pinfunction "20_20") (pintype "unspecified"))
      (node (ref "U4") (pin "7") (pinfunction "NO4_7") (pintype "unspecified"))
      (node (ref "U5") (pin "9") (pinfunction "NO2_9") (pintype "unspecified"))
      (node (ref "U9") (pin "31") (pinfunction "GPIO26_ADC0_31") (pintype "bidirectional"))
    )
    (net (code "88") (name "SCLK") (class "Default")
      (node (ref "P1") (pin "13") (pinfunction "13_13") (pintype "unspecified"))
      (node (ref "U8") (pin "12") (pinfunction "SCLK_12") (pintype "unspecified"))
    )
    (net (code "89") (name "START") (class "Default")
      (node (ref "U4") (pin "8") (pinfunction "COM_8") (pintype "unspecified"))
      (node (ref "U8") (pin "3") (pinfunction "START_3") (pintype "unspecified"))
    )
    (net (code "90") (name "STOP") (class "Default")
      (node (ref "U5") (pin "8") (pinfunction "COM_8") (pintype "unspecified"))
      (node (ref "U8") (pin "4") (pinfunction "STOP_4") (pintype "unspecified"))
    )
    (net (code "91") (name "Start_S0") (class "Default")
      (node (ref "U4") (pin "1") (pinfunction "A0_1") (pintype "unspecified"))
      (node (ref "U9") (pin "12") (pinfunction "GPIO9_12") (pintype "bidirectional"))
    )
    (net (code "92") (name "Start_S1") (class "Default")
      (node (ref "U4") (pin "10") (pinfunction "A1_10") (pintype "unspecified"))
      (node (ref "U9") (pin "11") (pinfunction "GPIO8_11") (pintype "bidirectional"))
    )
    (net (code "93") (name "Stop_S0") (class "Default")
      (node (ref "U5") (pin "1") (pinfunction "A0_1") (pintype "unspecified"))
      (node (ref "U9") (pin "10") (pinfunction "GPIO7_10") (pintype "bidirectional"))
    )
    (net (code "94") (name "Stop_S1") (class "Default")
      (node (ref "U5") (pin "10") (pinfunction "A1_10") (pintype "unspecified"))
      (node (ref "U9") (pin "9") (pinfunction "GPIO6_9") (pintype "bidirectional"))
    )
    (net (code "95") (name "SwClkSel1") (class "Default")
      (node (ref "P1") (pin "7") (pinfunction "7_7") (pintype "unspecified"))
      (node (ref "U16") (pin "1") (pinfunction "IN1_1") (pintype "unspecified"))
    )
    (net (code "96") (name "SwClkSel2") (class "Default")
      (node (ref "P1") (pin "5") (pinfunction "5_5") (pintype "unspecified"))
      (node (ref "U16") (pin "5") (pinfunction "IN2_5") (pintype "unspecified"))
    )
    (net (code "97") (name "TRIGG") (class "Default")
      (node (ref "P1") (pin "9") (pinfunction "9_9") (pintype "unspecified"))
      (node (ref "U8") (pin "2") (pinfunction "TRIGG_2") (pintype "unspecified"))
    )
    (net (code "98") (name "eiCLK") (class "Default")
      (node (ref "U16") (pin "10") (pinfunction "D1_10") (pintype "unspecified"))
      (node (ref "U16") (pin "4") (pinfunction "S2A_4") (pintype "unspecified"))
      (node (ref "U9") (pin "26") (pinfunction "GPIO20_26") (pintype "bidirectional"))
    )
    (net (code "99") (name "unconnected-(D4-NC-Pad2)") (class "Default")
      (node (ref "D4") (pin "2") (pinfunction "NC_2") (pintype "unspecified+no_connect"))
    )
    (net (code "100") (name "unconnected-(D5-NC-Pad2)") (class "Default")
      (node (ref "D5") (pin "2") (pinfunction "NC_2") (pintype "unspecified+no_connect"))
    )
    (net (code "101") (name "unconnected-(D15-NC-Pad2)") (class "Default")
      (node (ref "D15") (pin "2") (pinfunction "NC_2") (pintype "unspecified+no_connect"))
    )
    (net (code "102") (name "unconnected-(P2-NC-Pad1)") (class "Default")
      (node (ref "P2") (pin "1") (pinfunction "NC_1") (pintype "unspecified+no_connect"))
    )
    (net (code "103") (name "unconnected-(P2-NC-Pad5)") (class "Default")
      (node (ref "P2") (pin "5") (pinfunction "NC_5") (pintype "unspecified+no_connect"))
    )
    (net (code "104") (name "unconnected-(U3-N.C-Pad1)") (class "Default")
      (node (ref "U3") (pin "1") (pinfunction "N.C_1") (pintype "unspecified+no_connect"))
    )
    (net (code "105") (name "unconnected-(U8-N.C.-Pad6)") (class "Default")
      (node (ref "U8") (pin "6") (pinfunction "N.C._6") (pintype "unspecified+no_connect"))
    )
    (net (code "106") (name "unconnected-(U9-3V3_EN-Pad37)") (class "Default")
      (node (ref "U9") (pin "37") (pinfunction "3V3_EN_37") (pintype "input+no_connect"))
    )
    (net (code "107") (name "unconnected-(U9-ADC_VREF-Pad35)") (class "Default")
      (node (ref "U9") (pin "35") (pinfunction "ADC_VREF_35") (pintype "unspecified+no_connect"))
    )
    (net (code "108") (name "unconnected-(U9-AGND-Pad33)") (class "Default")
      (node (ref "U9") (pin "33") (pinfunction "AGND_33") (pintype "bidirectional+no_connect"))
    )
    (net (code "109") (name "unconnected-(U9-GND-Pad42)") (class "Default")
      (node (ref "U9") (pin "42") (pinfunction "GND_42") (pintype "bidirectional+no_connect"))
    )
    (net (code "110") (name "unconnected-(U9-GPIO0-Pad1)") (class "Default")
      (node (ref "U9") (pin "1") (pinfunction "GPIO0_1") (pintype "bidirectional+no_connect"))
    )
    (net (code "111") (name "unconnected-(U9-GPIO1-Pad2)") (class "Default")
      (node (ref "U9") (pin "2") (pinfunction "GPIO1_2") (pintype "bidirectional+no_connect"))
    )
    (net (code "112") (name "unconnected-(U9-GPIO12-Pad16)") (class "Default")
      (node (ref "U9") (pin "16") (pinfunction "GPIO12_16") (pintype "bidirectional+no_connect"))
    )
    (net (code "113") (name "unconnected-(U9-GPIO13-Pad17)") (class "Default")
      (node (ref "U9") (pin "17") (pinfunction "GPIO13_17") (pintype "bidirectional+no_connect"))
    )
    (net (code "114") (name "unconnected-(U9-GPIO14-Pad19)") (class "Default")
      (node (ref "U9") (pin "19") (pinfunction "GPIO14_19") (pintype "bidirectional+no_connect"))
    )
    (net (code "115") (name "unconnected-(U9-GPIO15-Pad20)") (class "Default")
      (node (ref "U9") (pin "20") (pinfunction "GPIO15_20") (pintype "bidirectional+no_connect"))
    )
    (net (code "116") (name "unconnected-(U9-GPIO16-Pad21)") (class "Default")
      (node (ref "U9") (pin "21") (pinfunction "GPIO16_21") (pintype "bidirectional+no_connect"))
    )
    (net (code "117") (name "unconnected-(U9-GPIO18-Pad24)") (class "Default")
      (node (ref "U9") (pin "24") (pinfunction "GPIO18_24") (pintype "bidirectional+no_connect"))
    )
    (net (code "118") (name "unconnected-(U9-GPIO19-Pad25)") (class "Default")
      (node (ref "U9") (pin "25") (pinfunction "GPIO19_25") (pintype "bidirectional+no_connect"))
    )
    (net (code "119") (name "unconnected-(U9-GPIO28_ADC2-Pad34)") (class "Default")
      (node (ref "U9") (pin "34") (pinfunction "GPIO28_ADC2_34") (pintype "bidirectional+no_connect"))
    )
    (net (code "120") (name "unconnected-(U9-RUN-Pad30)") (class "Default")
      (node (ref "U9") (pin "30") (pinfunction "RUN_30") (pintype "input+no_connect"))
    )
    (net (code "121") (name "unconnected-(U9-SWCLK-Pad41)") (class "Default")
      (node (ref "U9") (pin "41") (pinfunction "SWCLK_41") (pintype "input+no_connect"))
    )
    (net (code "122") (name "unconnected-(U9-SWDIO-Pad43)") (class "Default")
      (node (ref "U9") (pin "43") (pinfunction "SWDIO_43") (pintype "bidirectional+no_connect"))
    )
    (net (code "123") (name "unconnected-(U12-N.C-Pad1)") (class "Default")
      (node (ref "U12") (pin "1") (pinfunction "N.C_1") (pintype "unspecified+no_connect"))
    )
  )
)
